# mainBoard.net
KiCad netlist of a schematic drawn in EAGLE
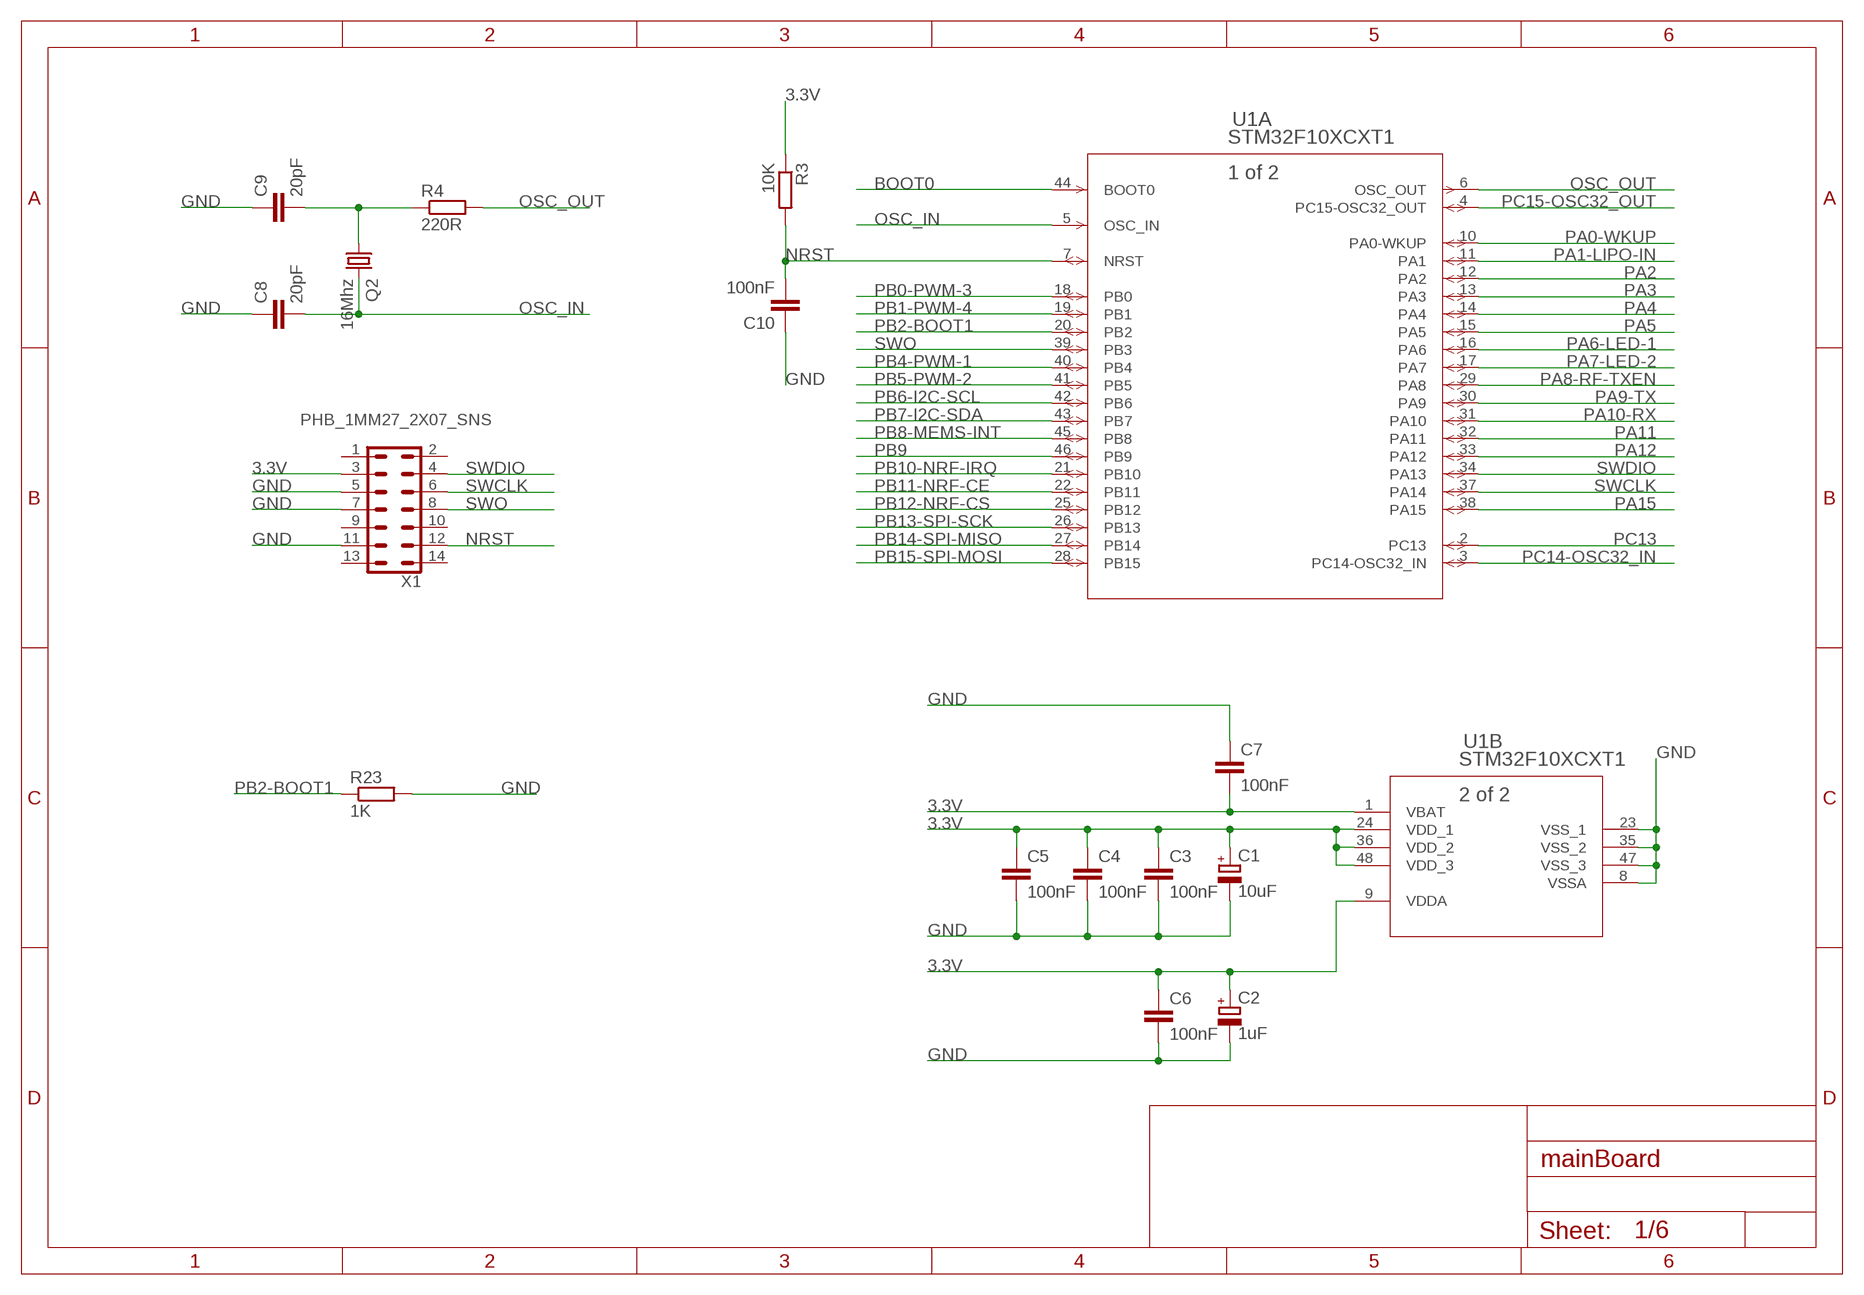
[diagram p0: schematic, sheet 1]
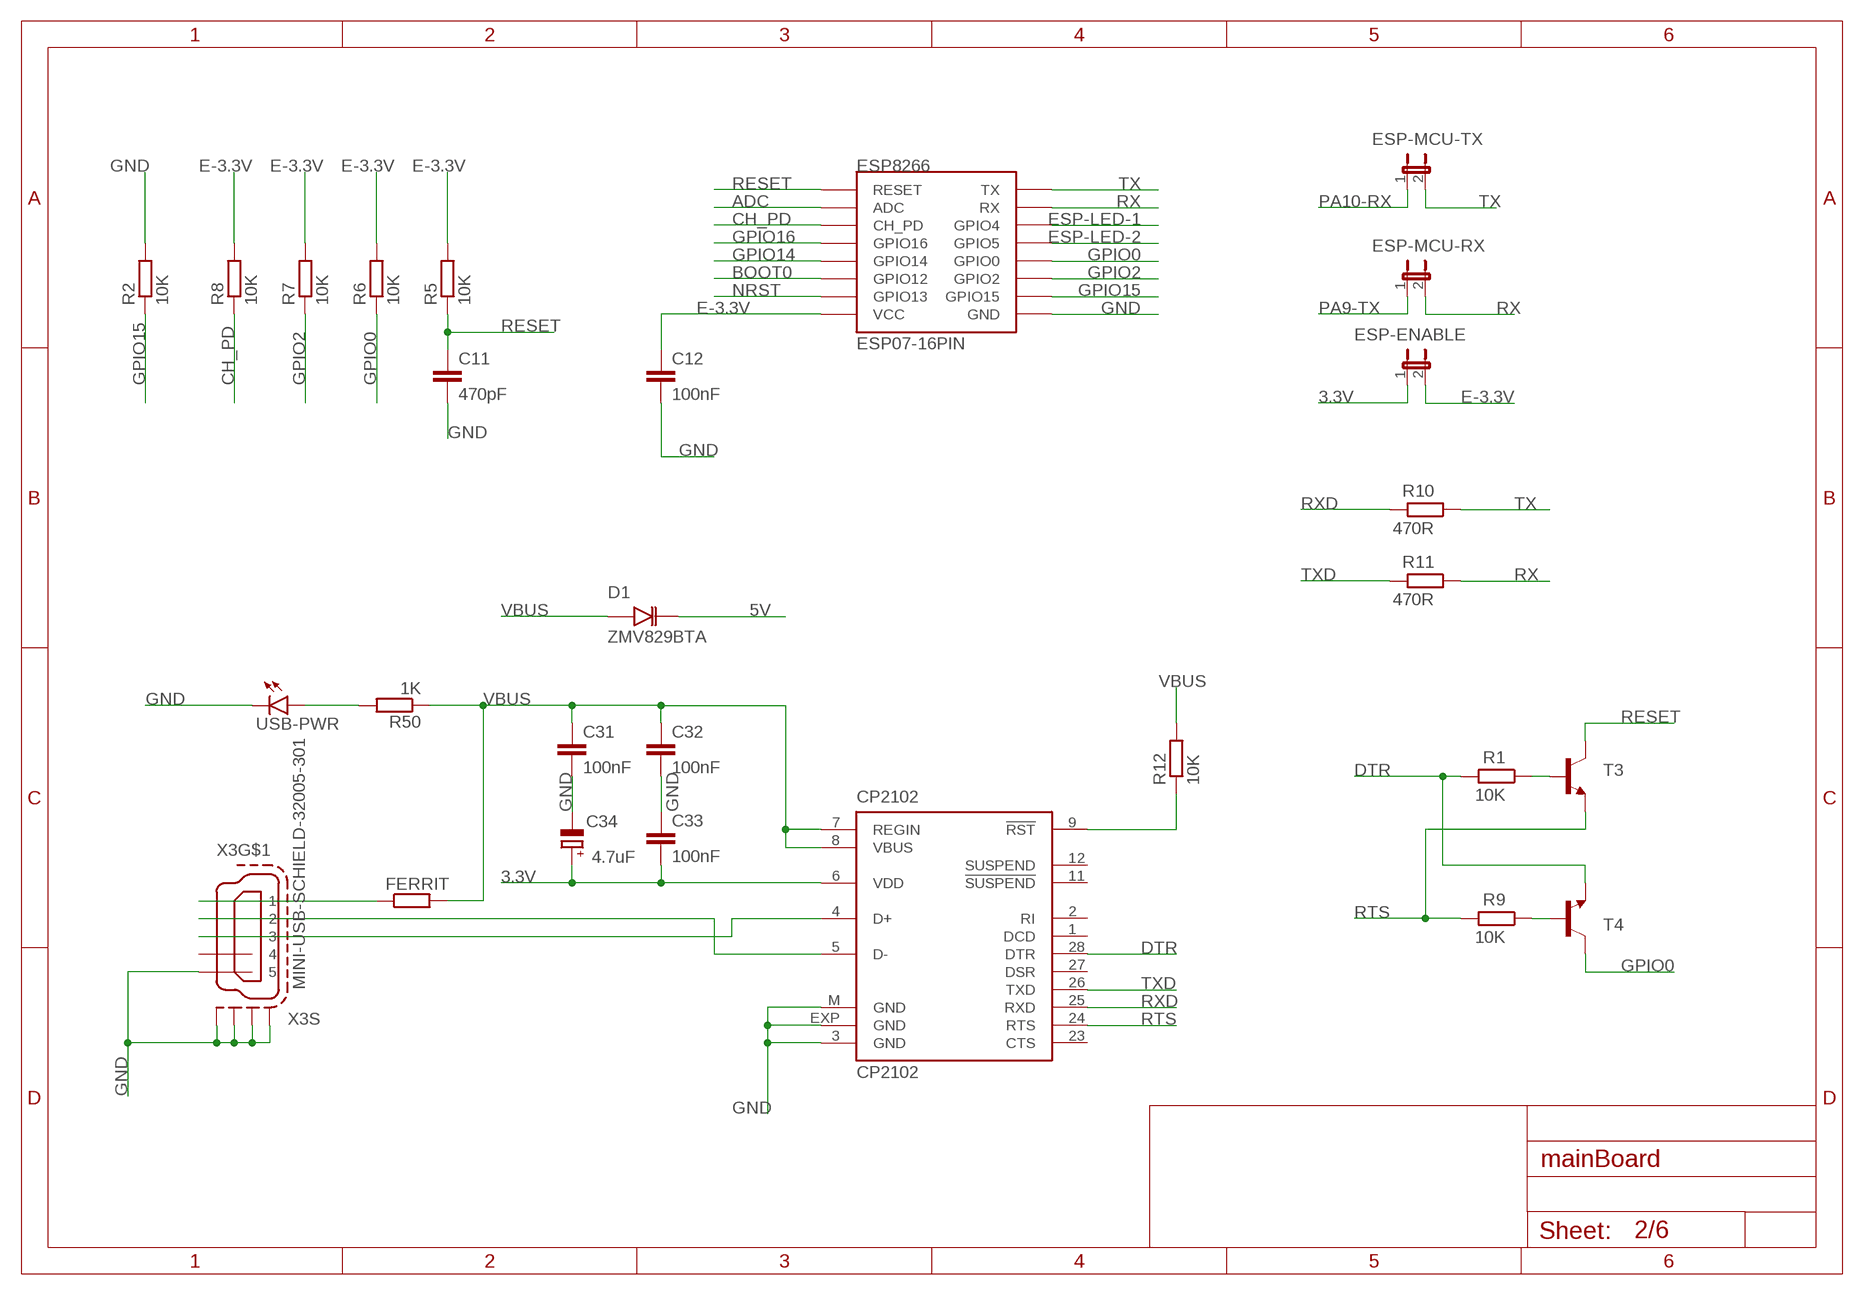
[diagram p1: schematic, sheet 2]
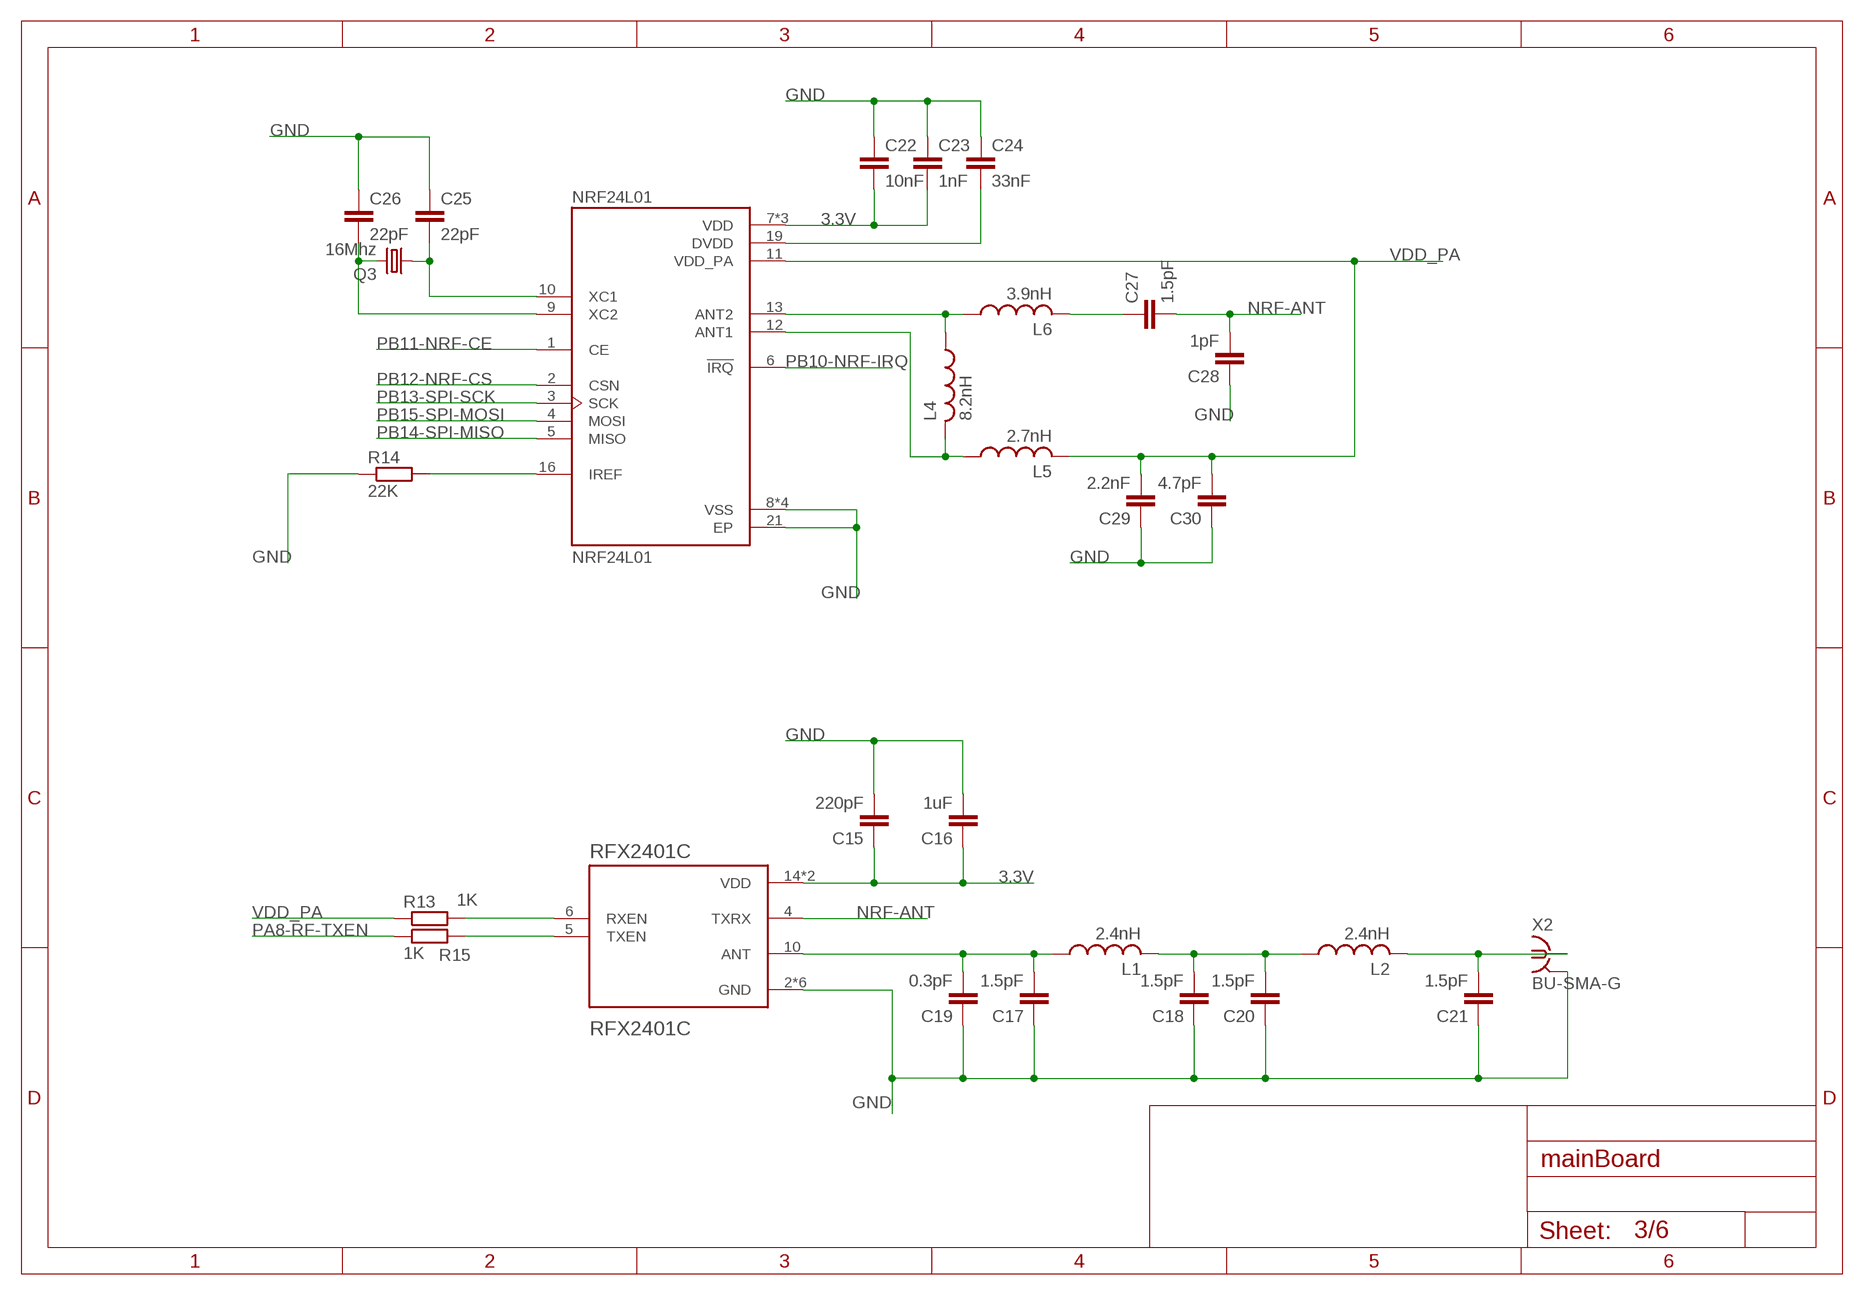
[diagram p2: schematic, sheet 3]
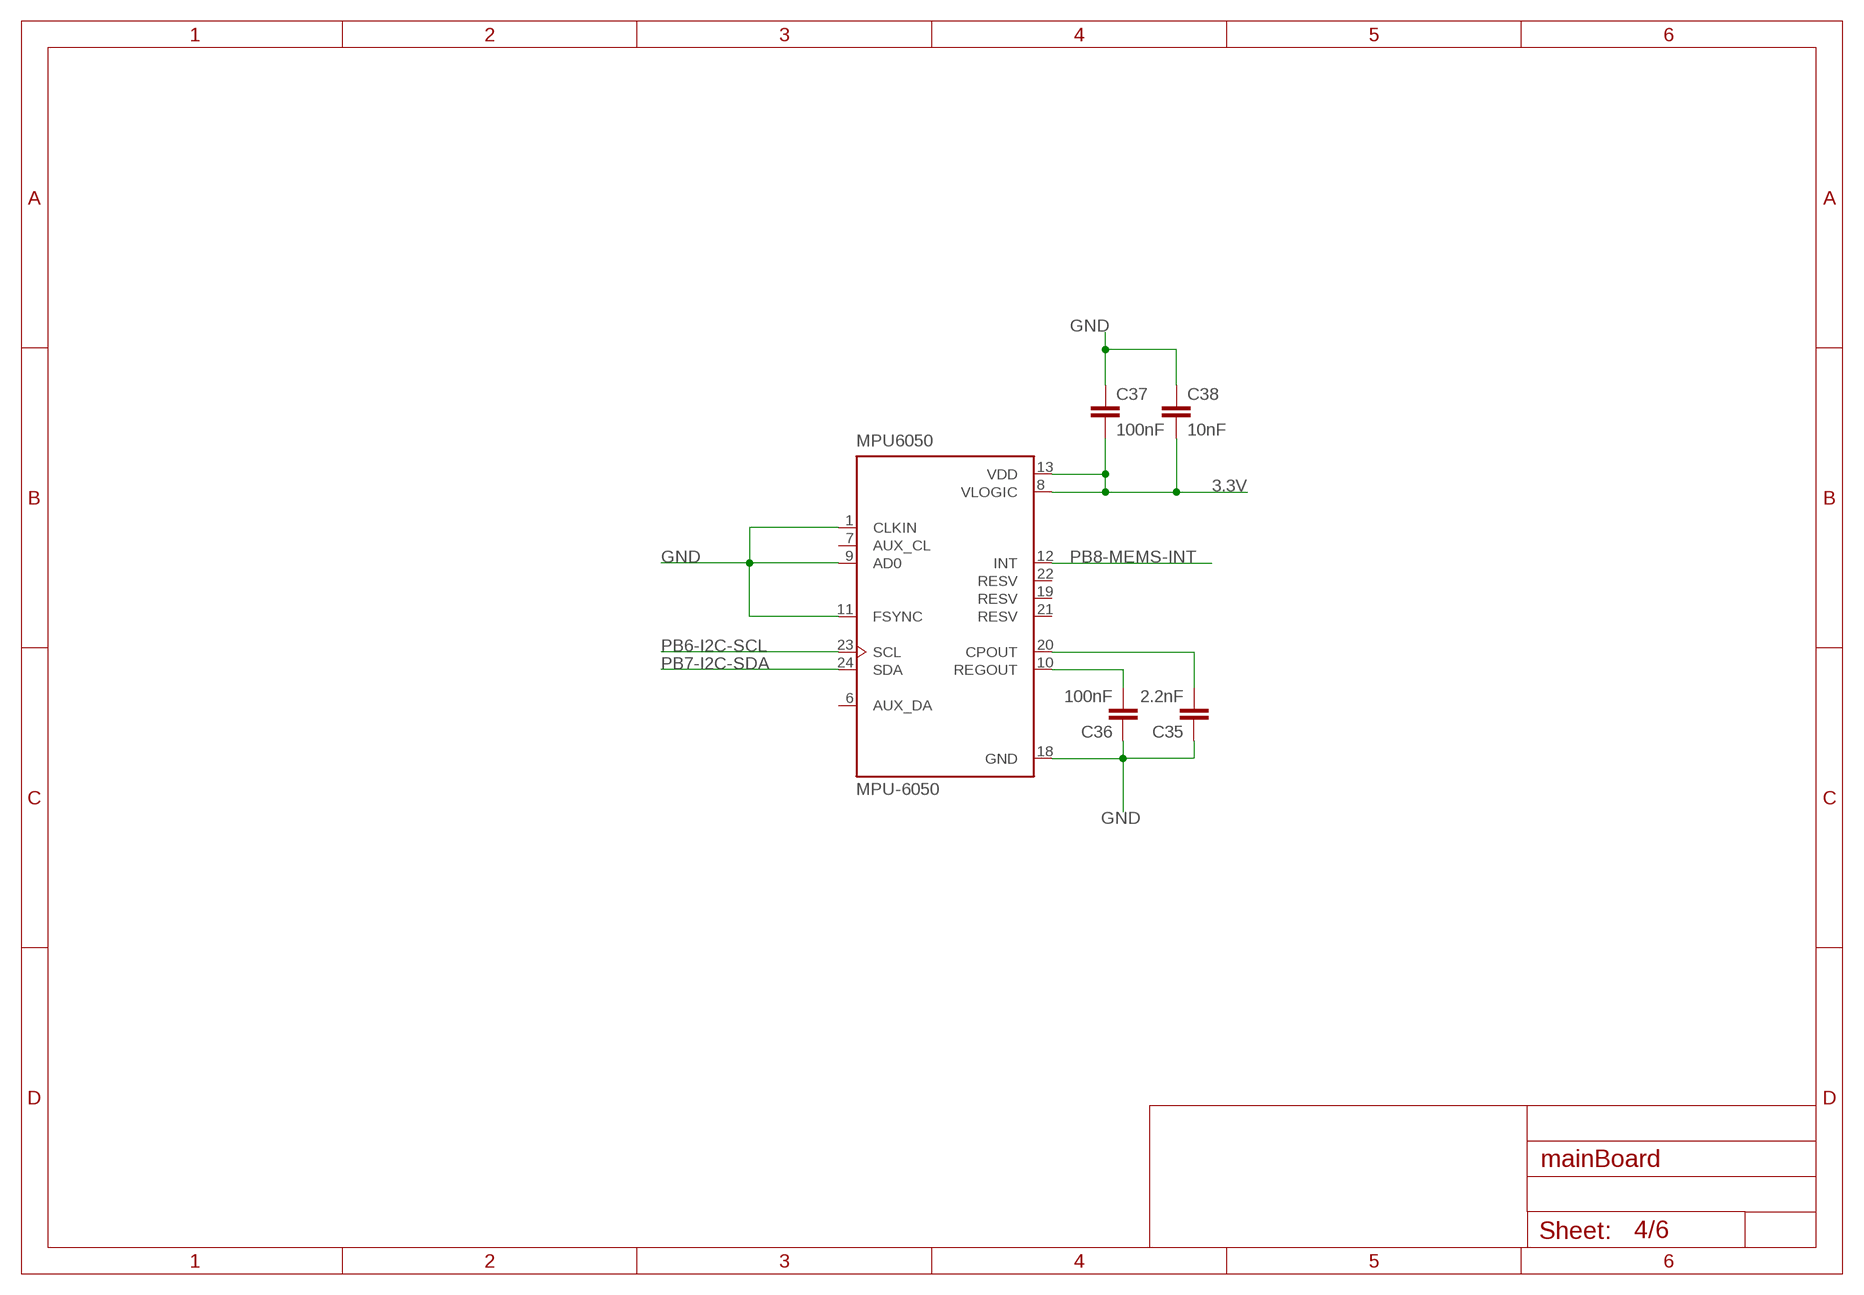
[diagram p3: schematic, sheet 4]
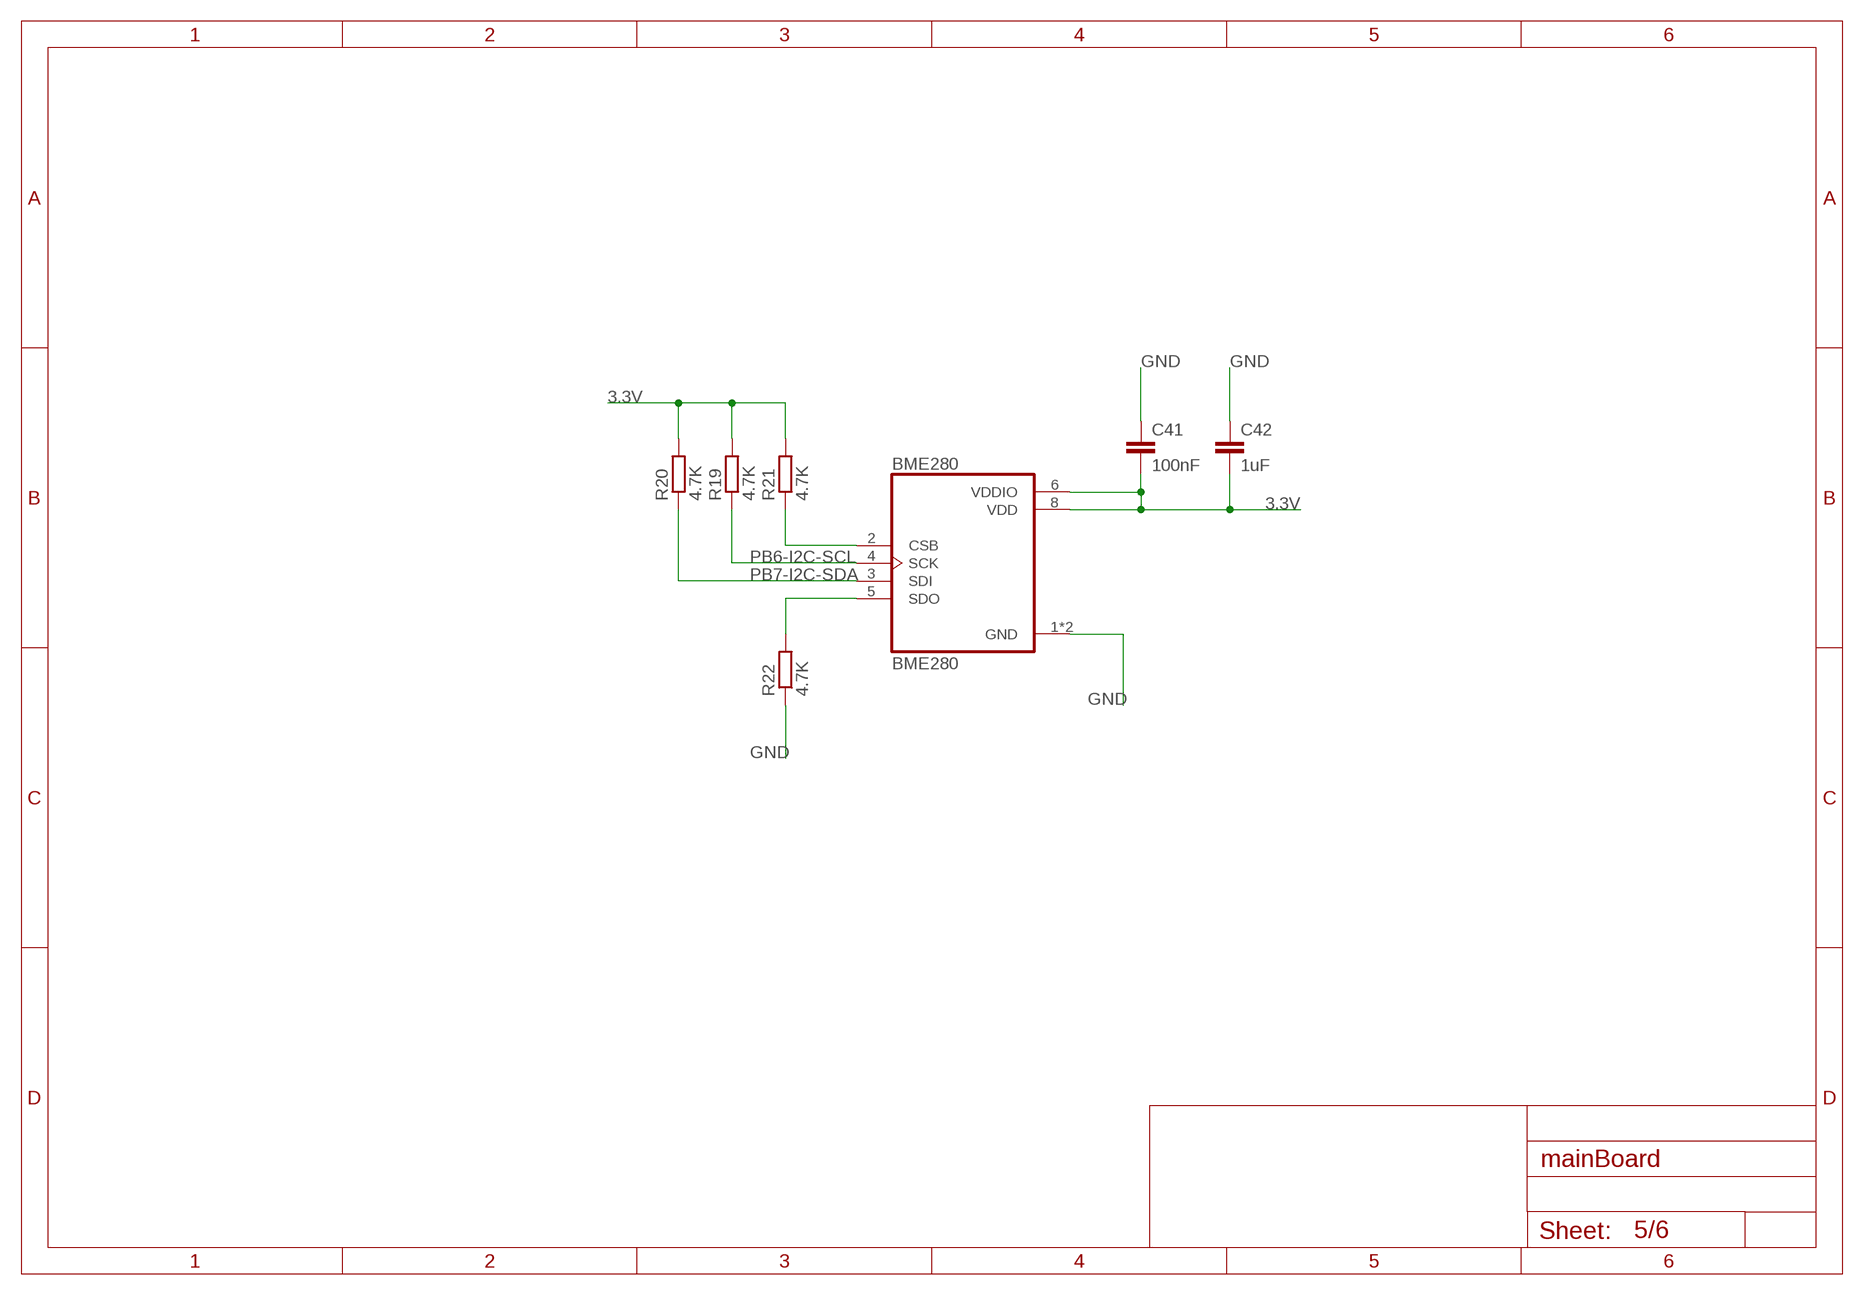
[diagram p4: schematic, sheet 5]
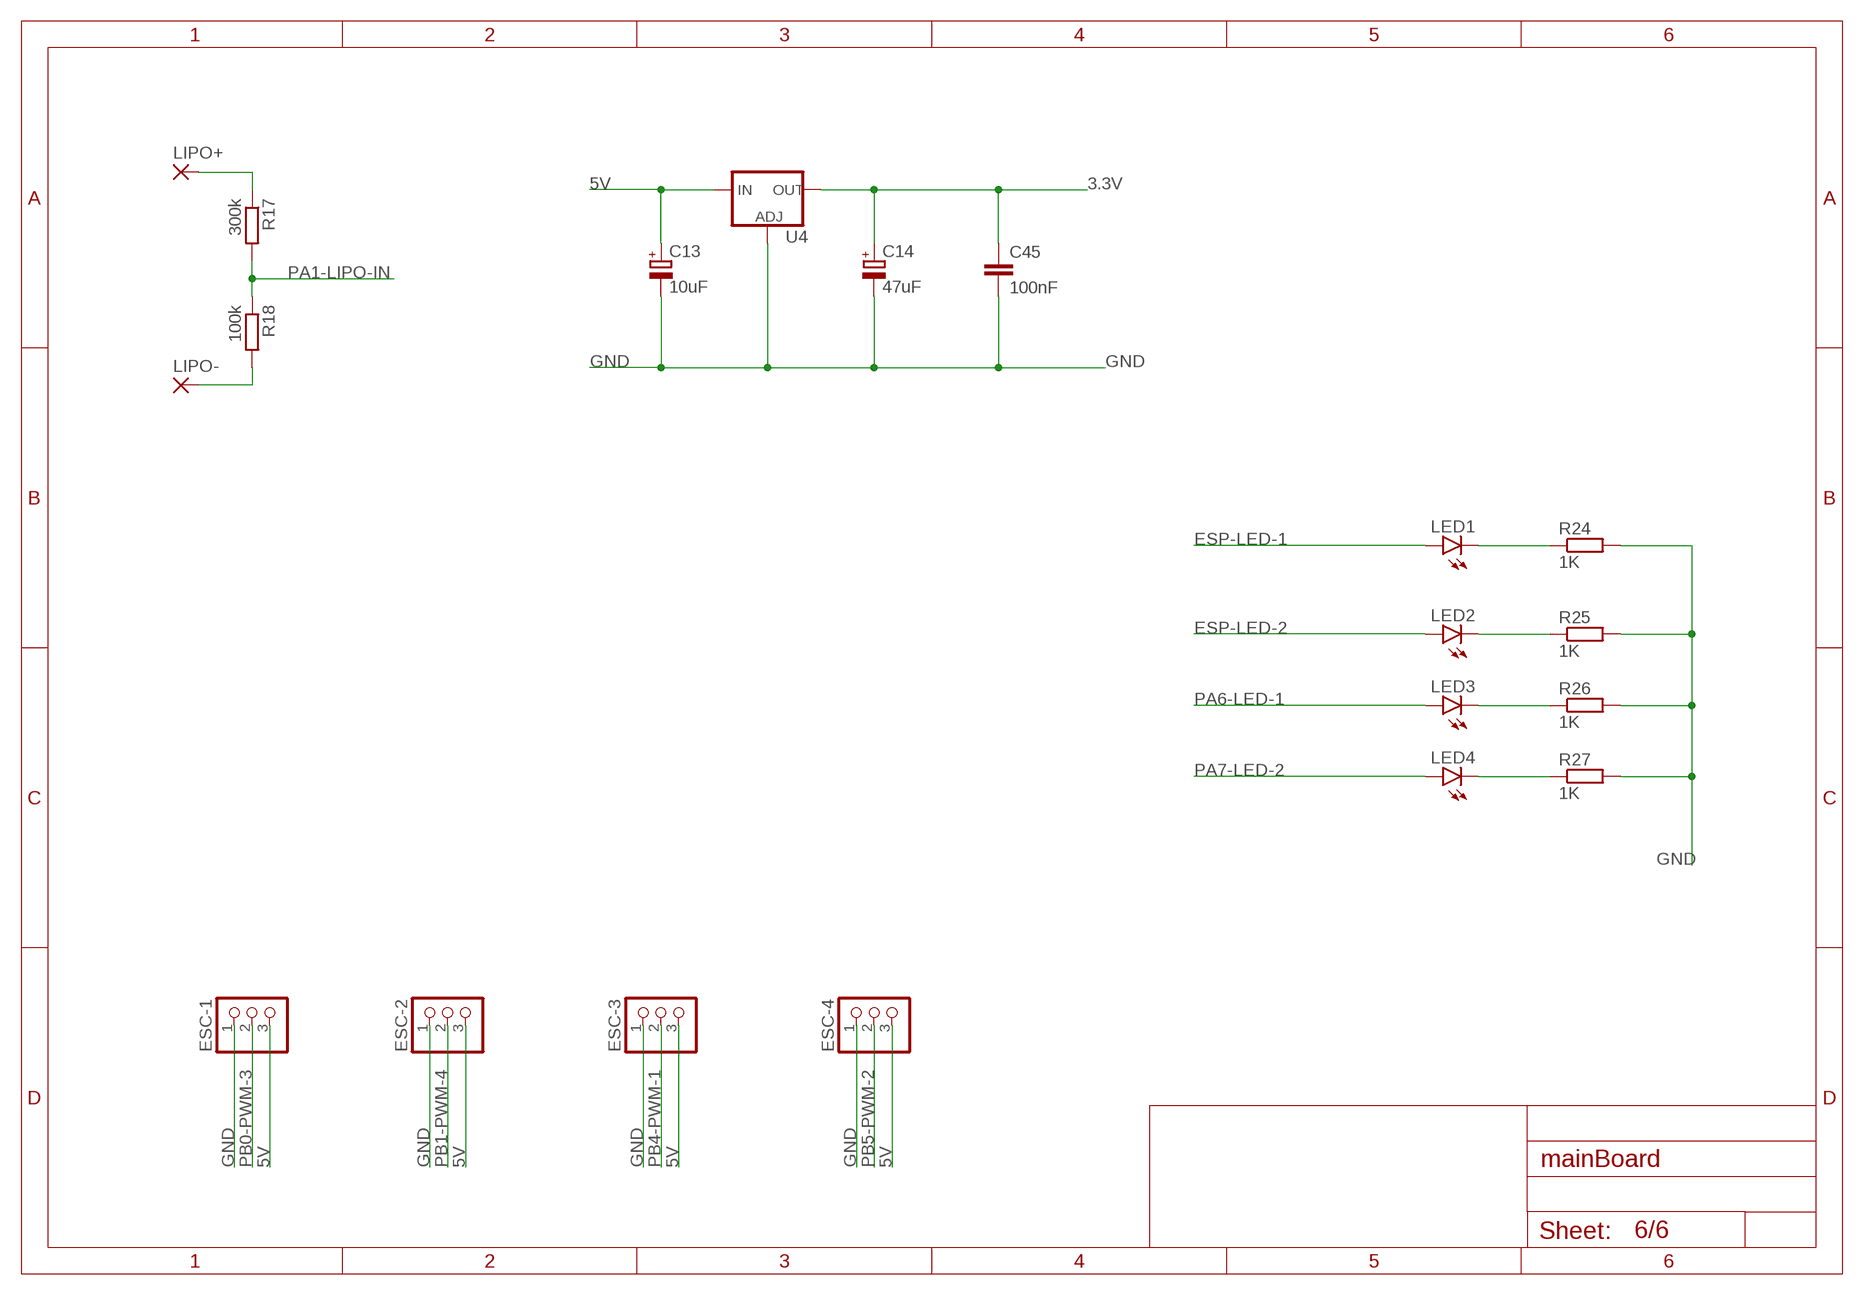
[diagram p5: schematic, sheet 6]

(export (version "E")
  (design (tool "Eeschema 10.0.6"))
  (components
    (comp (ref "C13")
      (value "10uF")
      (footprint "eagle-import:SMC_A")
      (libsource (lib "eagle-import") (part "CPOL-EUSMCA"))
    )
    (comp (ref "C14")
      (value "47uF")
      (footprint "eagle-import:SMC_A")
      (libsource (lib "eagle-import") (part "CPOL-EUSMCA"))
    )
    (comp (ref "C45")
      (value "100nF")
      (footprint "eagle-import:C0805")
      (libsource (lib "eagle-import") (part "C-EUC0805"))
    )
    (comp (ref "ESC-1")
      (value "PINHD-1X3")
      (footprint "eagle-import:1X03")
      (libsource (lib "eagle-import") (part "PINHD-1X3"))
    )
    (comp (ref "ESC-2")
      (value "PINHD-1X3")
      (footprint "eagle-import:1X03")
      (libsource (lib "eagle-import") (part "PINHD-1X3"))
    )
    (comp (ref "ESC-3")
      (value "PINHD-1X3")
      (footprint "eagle-import:1X03")
      (libsource (lib "eagle-import") (part "PINHD-1X3"))
    )
    (comp (ref "ESC-4")
      (value "PINHD-1X3")
      (footprint "eagle-import:1X03")
      (libsource (lib "eagle-import") (part "PINHD-1X3"))
    )
    (comp (ref "LED1")
      (value "LEDCHIPLED_0805")
      (footprint "eagle-import:CHIPLED_0805")
      (libsource (lib "eagle-import") (part "LEDCHIPLED_0805"))
    )
    (comp (ref "LED2")
      (value "LEDCHIPLED_0805")
      (footprint "eagle-import:CHIPLED_0805")
      (libsource (lib "eagle-import") (part "LEDCHIPLED_0805"))
    )
    (comp (ref "LED3")
      (value "LEDCHIPLED_0805")
      (footprint "eagle-import:CHIPLED_0805")
      (libsource (lib "eagle-import") (part "LEDCHIPLED_0805"))
    )
    (comp (ref "LED4")
      (value "LEDCHIPLED_0805")
      (footprint "eagle-import:CHIPLED_0805")
      (libsource (lib "eagle-import") (part "LEDCHIPLED_0805"))
    )
    (comp (ref "LIPO+")
      (value "2,15/1,0")
      (footprint "eagle-import:2,15_1,0")
      (libsource (lib "eagle-import") (part "2,15/1,0"))
    )
    (comp (ref "LIPO-")
      (value "2,15/1,0")
      (footprint "eagle-import:2,15_1,0")
      (libsource (lib "eagle-import") (part "2,15/1,0"))
    )
    (comp (ref "R17")
      (value "300k")
      (footprint "eagle-import:R0805")
      (libsource (lib "eagle-import") (part "R-EU_R0805"))
    )
    (comp (ref "R18")
      (value "100k")
      (footprint "eagle-import:R0805")
      (libsource (lib "eagle-import") (part "R-EU_R0805"))
    )
    (comp (ref "R24")
      (value "1K")
      (footprint "eagle-import:R0805")
      (libsource (lib "eagle-import") (part "R-EU_R0805"))
    )
    (comp (ref "R25")
      (value "1K")
      (footprint "eagle-import:R0805")
      (libsource (lib "eagle-import") (part "R-EU_R0805"))
    )
    (comp (ref "R26")
      (value "1K")
      (footprint "eagle-import:R0805")
      (libsource (lib "eagle-import") (part "R-EU_R0805"))
    )
    (comp (ref "R27")
      (value "1K")
      (footprint "eagle-import:R0805")
      (libsource (lib "eagle-import") (part "R-EU_R0805"))
    )
    (comp (ref "U4")
      (value "V_REG_LM1117SOT223")
      (footprint "eagle-import:SOT223")
      (libsource (lib "eagle-import") (part "V_REG_LM1117SOT223"))
    )
    (comp (ref "C11")
      (value "470pF")
      (footprint "eagle-import:C0805")
      (libsource (lib "eagle-import") (part "C-EUC0805"))
    )
    (comp (ref "C12")
      (value "100nF")
      (footprint "eagle-import:C0805")
      (libsource (lib "eagle-import") (part "C-EUC0805"))
    )
    (comp (ref "C31")
      (value "100nF")
      (footprint "eagle-import:C0805")
      (libsource (lib "eagle-import") (part "C-EUC0805"))
    )
    (comp (ref "C32")
      (value "100nF")
      (footprint "eagle-import:C0805")
      (libsource (lib "eagle-import") (part "C-EUC0805"))
    )
    (comp (ref "C33")
      (value "100nF")
      (footprint "eagle-import:C0805")
      (libsource (lib "eagle-import") (part "C-EUC0805"))
    )
    (comp (ref "C34")
      (value "4.7uF")
      (footprint "eagle-import:SMC_A")
      (libsource (lib "eagle-import") (part "CPOL-EUSMCA"))
    )
    (comp (ref "CP2102")
      (value "CP2102")
      (footprint "eagle-import:MLP28")
      (fields (field (name "MF") "FARNELL") (field (name "MPN") "CP2102-GM"))
      (libsource (lib "eagle-import") (part "CP2102"))
    )
    (comp (ref "D1")
      (value "ZMV829BTA")
      (footprint "eagle-import:SOD2512X116N")
      (fields (field (name "MF") "Diodes Inc."))
      (libsource (lib "eagle-import") (part "ZMV829BTA"))
    )
    (comp (ref "ESP-ENABLE")
      (value "JP1E")
      (footprint "eagle-import:JP1")
      (libsource (lib "eagle-import") (part "JP1E"))
    )
    (comp (ref "ESP-MCU-RX")
      (value "JP1E")
      (footprint "eagle-import:JP1")
      (libsource (lib "eagle-import") (part "JP1E"))
    )
    (comp (ref "ESP-MCU-TX")
      (value "JP1E")
      (footprint "eagle-import:JP1")
      (libsource (lib "eagle-import") (part "JP1E"))
    )
    (comp (ref "ESP8266")
      (value "ESP07-16PIN")
      (footprint "eagle-import:ESP07-16PIN")
      (libsource (lib "eagle-import") (part "ESP07-16PIN"))
    )
    (comp (ref "FERRIT")
      (value "R-EU_R0805")
      (footprint "eagle-import:R0805")
      (libsource (lib "eagle-import") (part "R-EU_R0805"))
    )
    (comp (ref "R1")
      (value "10K")
      (footprint "eagle-import:R0805")
      (libsource (lib "eagle-import") (part "R-EU_R0805"))
    )
    (comp (ref "R2")
      (value "10K")
      (footprint "eagle-import:R0805")
      (libsource (lib "eagle-import") (part "R-EU_R0805"))
    )
    (comp (ref "R5")
      (value "10K")
      (footprint "eagle-import:R0805")
      (libsource (lib "eagle-import") (part "R-EU_R0805"))
    )
    (comp (ref "R6")
      (value "10K")
      (footprint "eagle-import:R0805")
      (libsource (lib "eagle-import") (part "R-EU_R0805"))
    )
    (comp (ref "R7")
      (value "10K")
      (footprint "eagle-import:R0805")
      (libsource (lib "eagle-import") (part "R-EU_R0805"))
    )
    (comp (ref "R8")
      (value "10K")
      (footprint "eagle-import:R0805")
      (libsource (lib "eagle-import") (part "R-EU_R0805"))
    )
    (comp (ref "R9")
      (value "10K")
      (footprint "eagle-import:R0805")
      (libsource (lib "eagle-import") (part "R-EU_R0805"))
    )
    (comp (ref "R10")
      (value "470R")
      (footprint "eagle-import:R0805")
      (libsource (lib "eagle-import") (part "R-EU_R0805"))
    )
    (comp (ref "R11")
      (value "470R")
      (footprint "eagle-import:R0805")
      (libsource (lib "eagle-import") (part "R-EU_R0805"))
    )
    (comp (ref "R12")
      (value "10K")
      (footprint "eagle-import:R0805")
      (libsource (lib "eagle-import") (part "R-EU_R0805"))
    )
    (comp (ref "R50")
      (value "1K")
      (footprint "eagle-import:R0805")
      (libsource (lib "eagle-import") (part "R-EU_R0805"))
    )
    (comp (ref "T3")
      (value "-NPN-SOT23-EBC")
      (footprint "eagle-import:SOT23-EBC")
      (libsource (lib "eagle-import") (part "-NPN-SOT23-EBC"))
    )
    (comp (ref "T4")
      (value "-NPN-SOT23-EBC")
      (footprint "eagle-import:SOT23-EBC")
      (libsource (lib "eagle-import") (part "-NPN-SOT23-EBC"))
    )
    (comp (ref "USB-PWR")
      (value "LEDCHIPLED_0805")
      (footprint "eagle-import:CHIPLED_0805")
      (libsource (lib "eagle-import") (part "LEDCHIPLED_0805"))
    )
    (comp (ref "X3")
      (value "MINI-USB-SCHIELD-32005-301")
      (footprint "eagle-import:32005-301")
      (libsource (lib "eagle-import") (part "MINI-USB-SCHIELD-32005-301"))
    )
    (comp (ref "BME280")
      (value "BME280")
      (footprint "eagle-import:PSON65P250X250X100-8N")
      (fields (field (name "MF") "Bosch"))
      (libsource (lib "eagle-import") (part "BME280"))
    )
    (comp (ref "C41")
      (value "100nF")
      (footprint "eagle-import:C0805")
      (libsource (lib "eagle-import") (part "C-EUC0805"))
    )
    (comp (ref "C42")
      (value "1uF")
      (footprint "eagle-import:C0805")
      (libsource (lib "eagle-import") (part "C-EUC0805"))
    )
    (comp (ref "R19")
      (value "4.7K")
      (footprint "eagle-import:R0805")
      (libsource (lib "eagle-import") (part "R-EU_R0805"))
    )
    (comp (ref "R20")
      (value "4.7K")
      (footprint "eagle-import:R0805")
      (libsource (lib "eagle-import") (part "R-EU_R0805"))
    )
    (comp (ref "R21")
      (value "4.7K")
      (footprint "eagle-import:R0805")
      (libsource (lib "eagle-import") (part "R-EU_R0805"))
    )
    (comp (ref "R22")
      (value "4.7K")
      (footprint "eagle-import:R0805")
      (libsource (lib "eagle-import") (part "R-EU_R0805"))
    )
    (comp (ref "C1")
      (value "10uF")
      (footprint "eagle-import:SMC_A")
      (libsource (lib "eagle-import") (part "CPOL-EUSMCA"))
    )
    (comp (ref "C2")
      (value "1uF")
      (footprint "eagle-import:SMC_A")
      (libsource (lib "eagle-import") (part "CPOL-EUSMCA"))
    )
    (comp (ref "C3")
      (value "100nF")
      (footprint "eagle-import:C0805")
      (libsource (lib "eagle-import") (part "C-EUC0805"))
    )
    (comp (ref "C4")
      (value "100nF")
      (footprint "eagle-import:C0805")
      (libsource (lib "eagle-import") (part "C-EUC0805"))
    )
    (comp (ref "C5")
      (value "100nF")
      (footprint "eagle-import:C0805")
      (libsource (lib "eagle-import") (part "C-EUC0805"))
    )
    (comp (ref "C6")
      (value "100nF")
      (footprint "eagle-import:C0805")
      (libsource (lib "eagle-import") (part "C-EUC0805"))
    )
    (comp (ref "C7")
      (value "100nF")
      (footprint "eagle-import:C0805")
      (libsource (lib "eagle-import") (part "C-EUC0805"))
    )
    (comp (ref "C8")
      (value "20pF")
      (footprint "eagle-import:C0805")
      (libsource (lib "eagle-import") (part "C-EUC0805"))
    )
    (comp (ref "C9")
      (value "20pF")
      (footprint "eagle-import:C0805")
      (libsource (lib "eagle-import") (part "C-EUC0805"))
    )
    (comp (ref "C10")
      (value "100nF")
      (footprint "eagle-import:C0805")
      (libsource (lib "eagle-import") (part "C-EUC0805"))
    )
    (comp (ref "Q2")
      (value "16Mhz")
      (footprint "eagle-import:HC49_S")
      (libsource (lib "eagle-import") (part "CRYSTALHC49S"))
    )
    (comp (ref "R3")
      (value "10K")
      (footprint "eagle-import:R0805")
      (libsource (lib "eagle-import") (part "R-EU_R0805"))
    )
    (comp (ref "R4")
      (value "220R")
      (footprint "eagle-import:R0805")
      (libsource (lib "eagle-import") (part "R-EU_R0805"))
    )
    (comp (ref "R23")
      (value "1K")
      (footprint "eagle-import:R0805")
      (libsource (lib "eagle-import") (part "R-EU_R0805"))
    )
    (comp (ref "U1")
      (value "STM32F10XCXT1")
      (footprint "eagle-import:LQFP48-7X7MM")
      (fields (field (name "COPYRIGHT") "Copyright (C) 2016 Accelerated Designs. All rights reserved"))
      (libsource (lib "eagle-import") (part "STM32F10XCXT1"))
    )
    (comp (ref "X1")
      (value "PHB_1MM27_2X07_SNS")
      (footprint "eagle-import:PHB_1MM27_2X07_SNS")
      (libsource (lib "eagle-import") (part "PHB_1MM27_2X07_SNS"))
    )
    (comp (ref "C35")
      (value "2.2nF")
      (footprint "eagle-import:C0805")
      (libsource (lib "eagle-import") (part "C-EUC0805"))
    )
    (comp (ref "C36")
      (value "100nF")
      (footprint "eagle-import:C0805")
      (libsource (lib "eagle-import") (part "C-EUC0805"))
    )
    (comp (ref "C37")
      (value "100nF")
      (footprint "eagle-import:C0805")
      (libsource (lib "eagle-import") (part "C-EUC0805"))
    )
    (comp (ref "C38")
      (value "10nF")
      (footprint "eagle-import:C0805")
      (libsource (lib "eagle-import") (part "C-EUC0805"))
    )
    (comp (ref "MPU6050")
      (value "MPU-6050")
      (footprint "eagle-import:QFN50P400X400X95-24N")
      (fields (field (name "MF") "TDK InvenSense"))
      (libsource (lib "eagle-import") (part "MPU-6050"))
    )
    (comp (ref "C15")
      (value "220pF")
      (footprint "eagle-import:C0805")
      (libsource (lib "eagle-import") (part "C-EUC0805"))
    )
    (comp (ref "C16")
      (value "1uF")
      (footprint "eagle-import:C0805")
      (libsource (lib "eagle-import") (part "C-EUC0805"))
    )
    (comp (ref "C17")
      (value "1.5pF")
      (footprint "eagle-import:C0805")
      (libsource (lib "eagle-import") (part "C-EUC0805"))
    )
    (comp (ref "C18")
      (value "1.5pF")
      (footprint "eagle-import:C0805")
      (libsource (lib "eagle-import") (part "C-EUC0805"))
    )
    (comp (ref "C19")
      (value "0.3pF")
      (footprint "eagle-import:C0805")
      (libsource (lib "eagle-import") (part "C-EUC0805"))
    )
    (comp (ref "C20")
      (value "1.5pF")
      (footprint "eagle-import:C0805")
      (libsource (lib "eagle-import") (part "C-EUC0805"))
    )
    (comp (ref "C21")
      (value "1.5pF")
      (footprint "eagle-import:C0805")
      (libsource (lib "eagle-import") (part "C-EUC0805"))
    )
    (comp (ref "C22")
      (value "10nF")
      (footprint "eagle-import:C0805")
      (libsource (lib "eagle-import") (part "C-EUC0805"))
    )
    (comp (ref "C23")
      (value "1nF")
      (footprint "eagle-import:C0805")
      (libsource (lib "eagle-import") (part "C-EUC0805"))
    )
    (comp (ref "C24")
      (value "33nF")
      (footprint "eagle-import:C0805")
      (libsource (lib "eagle-import") (part "C-EUC0805"))
    )
    (comp (ref "C25")
      (value "22pF")
      (footprint "eagle-import:C0805")
      (libsource (lib "eagle-import") (part "C-EUC0805"))
    )
    (comp (ref "C26")
      (value "22pF")
      (footprint "eagle-import:C0805")
      (libsource (lib "eagle-import") (part "C-EUC0805"))
    )
    (comp (ref "C27")
      (value "1.5pF")
      (footprint "eagle-import:C0805")
      (libsource (lib "eagle-import") (part "C-EUC0805"))
    )
    (comp (ref "C28")
      (value "1pF")
      (footprint "eagle-import:C0805")
      (libsource (lib "eagle-import") (part "C-EUC0805"))
    )
    (comp (ref "C29")
      (value "2.2nF")
      (footprint "eagle-import:C0805")
      (libsource (lib "eagle-import") (part "C-EUC0805"))
    )
    (comp (ref "C30")
      (value "4.7pF")
      (footprint "eagle-import:C0805")
      (libsource (lib "eagle-import") (part "C-EUC0805"))
    )
    (comp (ref "L1")
      (value "2.4nH")
      (footprint "eagle-import:L2012C")
      (libsource (lib "eagle-import") (part "L-USL2012C"))
    )
    (comp (ref "L2")
      (value "2.4nH")
      (footprint "eagle-import:L2012C")
      (libsource (lib "eagle-import") (part "L-USL2012C"))
    )
    (comp (ref "L4")
      (value "8.2nH")
      (footprint "eagle-import:L2012C")
      (libsource (lib "eagle-import") (part "L-USL2012C"))
    )
    (comp (ref "L5")
      (value "2.7nH")
      (footprint "eagle-import:L2012C")
      (libsource (lib "eagle-import") (part "L-USL2012C"))
    )
    (comp (ref "L6")
      (value "3.9nH")
      (footprint "eagle-import:L2012C")
      (libsource (lib "eagle-import") (part "L-USL2012C"))
    )
    (comp (ref "NRF24L01")
      (value "NRF24L01")
      (footprint "eagle-import:QFN50P400X400X95-21N")
      (fields (field (name "MF") "Nordic"))
      (libsource (lib "eagle-import") (part "NRF24L01"))
    )
    (comp (ref "Q3")
      (value "16Mhz")
      (footprint "eagle-import:HC49_S")
      (libsource (lib "eagle-import") (part "CRYSTALHC49S"))
    )
    (comp (ref "R13")
      (value "1K")
      (footprint "eagle-import:R0805")
      (libsource (lib "eagle-import") (part "R-EU_R0805"))
    )
    (comp (ref "R14")
      (value "22K")
      (footprint "eagle-import:R0805")
      (libsource (lib "eagle-import") (part "R-EU_R0805"))
    )
    (comp (ref "R15")
      (value "1K")
      (footprint "eagle-import:R0805")
      (libsource (lib "eagle-import") (part "R-EU_R0805"))
    )
    (comp (ref "RFX2401C")
      (value "RFX2401C")
      (footprint "eagle-import:QFN50P300X300X60-17N")
      (fields (field (name "MF") "Skyworks Solutions"))
      (libsource (lib "eagle-import") (part "RFX2401C"))
    )
    (comp (ref "X2")
      (value "BU-SMA-G")
      (footprint "eagle-import:BU-SMA-G")
      (libsource (lib "eagle-import") (part "BU-SMA-G"))
    )
  )
  (nets
    (net (code "1") (name "3.3V") (class "Default")
      (node (ref "BME280") (pin "6") (pinfunction "VDDIO_6") (pintype "power_in"))
      (node (ref "BME280") (pin "8") (pinfunction "VDD_8") (pintype "power_in"))
      (node (ref "C1") (pin "+") (pinfunction "+_+") (pintype "passive"))
      (node (ref "C14") (pin "+") (pinfunction "+_+") (pintype "passive"))
      (node (ref "C15") (pin "1") (pinfunction "1_1") (pintype "passive"))
      (node (ref "C16") (pin "1") (pinfunction "1_1") (pintype "passive"))
      (node (ref "C2") (pin "+") (pinfunction "+_+") (pintype "passive"))
      (node (ref "C22") (pin "2") (pinfunction "2_2") (pintype "passive"))
      (node (ref "C23") (pin "2") (pinfunction "2_2") (pintype "passive"))
      (node (ref "C3") (pin "1") (pinfunction "1_1") (pintype "passive"))
      (node (ref "C33") (pin "2") (pinfunction "2_2") (pintype "passive"))
      (node (ref "C34") (pin "+") (pinfunction "+_+") (pintype "passive"))
      (node (ref "C37") (pin "2") (pinfunction "2_2") (pintype "passive"))
      (node (ref "C38") (pin "2") (pinfunction "2_2") (pintype "passive"))
      (node (ref "C4") (pin "1") (pinfunction "1_1") (pintype "passive"))
      (node (ref "C41") (pin "2") (pinfunction "2_2") (pintype "passive"))
      (node (ref "C42") (pin "2") (pinfunction "2_2") (pintype "passive"))
      (node (ref "C45") (pin "1") (pinfunction "1_1") (pintype "passive"))
      (node (ref "C5") (pin "1") (pinfunction "1_1") (pintype "passive"))
      (node (ref "C6") (pin "1") (pinfunction "1_1") (pintype "passive"))
      (node (ref "C7") (pin "2") (pinfunction "2_2") (pintype "passive"))
      (node (ref "CP2102") (pin "6") (pinfunction "VDD_6") (pintype "power_in"))
      (node (ref "ESP-ENABLE") (pin "1") (pinfunction "1_1") (pintype "passive"))
      (node (ref "MPU6050") (pin "13") (pinfunction "VDD_13") (pintype "power_in"))
      (node (ref "MPU6050") (pin "8") (pinfunction "VLOGIC_8") (pintype "power_in"))
      (node (ref "NRF24L01") (pin "15") (pinfunction "VDD_15") (pintype "power_in"))
      (node (ref "NRF24L01") (pin "18") (pinfunction "VDD_18") (pintype "power_in"))
      (node (ref "NRF24L01") (pin "7") (pinfunction "VDD_7") (pintype "power_in"))
      (node (ref "R19") (pin "2") (pinfunction "2_2") (pintype "passive"))
      (node (ref "R20") (pin "2") (pinfunction "2_2") (pintype "passive"))
      (node (ref "R21") (pin "2") (pinfunction "2_2") (pintype "passive"))
      (node (ref "R3") (pin "1") (pinfunction "1_1") (pintype "passive"))
      (node (ref "RFX2401C") (pin "14") (pinfunction "VDD_14") (pintype "power_in"))
      (node (ref "RFX2401C") (pin "16") (pinfunction "VDD_16") (pintype "power_in"))
      (node (ref "U1") (pin "1") (pinfunction "VBAT_1") (pintype "power_in"))
      (node (ref "U1") (pin "24") (pinfunction "VDD_1_24") (pintype "power_in"))
      (node (ref "U1") (pin "36") (pinfunction "VDD_2_36") (pintype "power_in"))
      (node (ref "U1") (pin "48") (pinfunction "VDD_3_48") (pintype "power_in"))
      (node (ref "U1") (pin "9") (pinfunction "VDDA_9") (pintype "power_in"))
      (node (ref "U4") (pin "2") (pinfunction "OUT_2") (pintype "output"))
      (node (ref "U4") (pin "4") (pinfunction "OUT_4") (pintype "output"))
      (node (ref "X1") (pin "3") (pinfunction "3_3") (pintype "passive"))
    )
    (net (code "2") (name "5V") (class "Default")
      (node (ref "C13") (pin "+") (pinfunction "+_+") (pintype "passive"))
      (node (ref "D1") (pin "K") (pinfunction "K_K") (pintype "passive"))
      (node (ref "ESC-1") (pin "3") (pinfunction "3_3") (pintype "passive"))
      (node (ref "ESC-2") (pin "3") (pinfunction "3_3") (pintype "passive"))
      (node (ref "ESC-3") (pin "3") (pinfunction "3_3") (pintype "passive"))
      (node (ref "ESC-4") (pin "3") (pinfunction "3_3") (pintype "passive"))
      (node (ref "U4") (pin "3") (pinfunction "IN_3") (pintype "input"))
    )
    (net (code "3") (name "ADC") (class "Default")
      (node (ref "ESP8266") (pin "ADC") (pinfunction "ADC_ADC") (pintype "bidirectional"))
    )
    (net (code "4") (name "BOOT0") (class "Default")
      (node (ref "ESP8266") (pin "GPIO12") (pinfunction "GPIO12_GPIO12") (pintype "bidirectional"))
      (node (ref "U1") (pin "44") (pinfunction "BOOT0_44") (pintype "input"))
    )
    (net (code "5") (name "CH_PD") (class "Default")
      (node (ref "ESP8266") (pin "CH_PD") (pinfunction "CH_PD_CH_PD") (pintype "bidirectional"))
      (node (ref "R8") (pin "1") (pinfunction "1_1") (pintype "passive"))
    )
    (net (code "6") (name "DTR") (class "Default")
      (node (ref "CP2102") (pin "28") (pinfunction "DTR_28") (pintype "output"))
      (node (ref "R1") (pin "2") (pinfunction "2_2") (pintype "passive"))
      (node (ref "T4") (pin "E") (pinfunction "E_E") (pintype "passive"))
    )
    (net (code "7") (name "E-3.3V") (class "Default")
      (node (ref "C12") (pin "1") (pinfunction "1_1") (pintype "passive"))
      (node (ref "ESP-ENABLE") (pin "2") (pinfunction "2_2") (pintype "passive"))
      (node (ref "ESP8266") (pin "VCC") (pinfunction "VCC_VCC") (pintype "bidirectional"))
      (node (ref "R5") (pin "2") (pinfunction "2_2") (pintype "passive"))
      (node (ref "R6") (pin "2") (pinfunction "2_2") (pintype "passive"))
      (node (ref "R7") (pin "2") (pinfunction "2_2") (pintype "passive"))
      (node (ref "R8") (pin "2") (pinfunction "2_2") (pintype "passive"))
    )
    (net (code "8") (name "ESP-LED-1") (class "Default")
      (node (ref "ESP8266") (pin "GPIO4") (pinfunction "GPIO4_GPIO4") (pintype "bidirectional"))
      (node (ref "LED1") (pin "A") (pinfunction "A_A") (pintype "passive"))
    )
    (net (code "9") (name "ESP-LED-2") (class "Default")
      (node (ref "ESP8266") (pin "GPIO5") (pinfunction "GPIO5_GPIO5") (pintype "bidirectional"))
      (node (ref "LED2") (pin "A") (pinfunction "A_A") (pintype "passive"))
    )
    (net (code "10") (name "GND") (class "Default")
      (node (ref "BME280") (pin "1") (pinfunction "GND_1") (pintype "power_in"))
      (node (ref "BME280") (pin "7") (pinfunction "GND_7") (pintype "power_in"))
      (node (ref "C1") (pin "-") (pinfunction "-_-") (pintype "passive"))
      (node (ref "C10") (pin "1") (pinfunction "1_1") (pintype "passive"))
      (node (ref "C11") (pin "2") (pinfunction "2_2") (pintype "passive"))
      (node (ref "C12") (pin "2") (pinfunction "2_2") (pintype "passive"))
      (node (ref "C13") (pin "-") (pinfunction "-_-") (pintype "passive"))
      (node (ref "C14") (pin "-") (pinfunction "-_-") (pintype "passive"))
      (node (ref "C15") (pin "2") (pinfunction "2_2") (pintype "passive"))
      (node (ref "C16") (pin "2") (pinfunction "2_2") (pintype "passive"))
      (node (ref "C17") (pin "1") (pinfunction "1_1") (pintype "passive"))
      (node (ref "C18") (pin "1") (pinfunction "1_1") (pintype "passive"))
      (node (ref "C19") (pin "1") (pinfunction "1_1") (pintype "passive"))
      (node (ref "C2") (pin "-") (pinfunction "-_-") (pintype "passive"))
      (node (ref "C20") (pin "1") (pinfunction "1_1") (pintype "passive"))
      (node (ref "C21") (pin "1") (pinfunction "1_1") (pintype "passive"))
      (node (ref "C22") (pin "1") (pinfunction "1_1") (pintype "passive"))
      (node (ref "C23") (pin "1") (pinfunction "1_1") (pintype "passive"))
      (node (ref "C24") (pin "1") (pinfunction "1_1") (pintype "passive"))
      (node (ref "C25") (pin "1") (pinfunction "1_1") (pintype "passive"))
      (node (ref "C26") (pin "1") (pinfunction "1_1") (pintype "passive"))
      (node (ref "C28") (pin "1") (pinfunction "1_1") (pintype "passive"))
      (node (ref "C29") (pin "1") (pinfunction "1_1") (pintype "passive"))
      (node (ref "C3") (pin "2") (pinfunction "2_2") (pintype "passive"))
      (node (ref "C30") (pin "1") (pinfunction "1_1") (pintype "passive"))
      (node (ref "C31") (pin "2") (pinfunction "2_2") (pintype "passive"))
      (node (ref "C32") (pin "2") (pinfunction "2_2") (pintype "passive"))
      (node (ref "C33") (pin "1") (pinfunction "1_1") (pintype "passive"))
      (node (ref "C34") (pin "-") (pinfunction "-_-") (pintype "passive"))
      (node (ref "C35") (pin "1") (pinfunction "1_1") (pintype "passive"))
      (node (ref "C36") (pin "1") (pinfunction "1_1") (pintype "passive"))
      (node (ref "C37") (pin "1") (pinfunction "1_1") (pintype "passive"))
      (node (ref "C38") (pin "1") (pinfunction "1_1") (pintype "passive"))
      (node (ref "C4") (pin "2") (pinfunction "2_2") (pintype "passive"))
      (node (ref "C41") (pin "1") (pinfunction "1_1") (pintype "passive"))
      (node (ref "C42") (pin "1") (pinfunction "1_1") (pintype "passive"))
      (node (ref "C45") (pin "2") (pinfunction "2_2") (pintype "passive"))
      (node (ref "C5") (pin "2") (pinfunction "2_2") (pintype "passive"))
      (node (ref "C6") (pin "2") (pinfunction "2_2") (pintype "passive"))
      (node (ref "C7") (pin "1") (pinfunction "1_1") (pintype "passive"))
      (node (ref "C8") (pin "1") (pinfunction "1_1") (pintype "passive"))
      (node (ref "C9") (pin "1") (pinfunction "1_1") (pintype "passive"))
      (node (ref "CP2102") (pin "3") (pinfunction "GND_3") (pintype "power_in"))
      (node (ref "CP2102") (pin "EXP") (pinfunction "GND_EXP") (pintype "power_in"))
      (node (ref "CP2102") (pin "M") (pinfunction "GND_M") (pintype "power_in"))
      (node (ref "ESC-1") (pin "1") (pinfunction "1_1") (pintype "passive"))
      (node (ref "ESC-2") (pin "1") (pinfunction "1_1") (pintype "passive"))
      (node (ref "ESC-3") (pin "1") (pinfunction "1_1") (pintype "passive"))
      (node (ref "ESC-4") (pin "1") (pinfunction "1_1") (pintype "passive"))
      (node (ref "ESP8266") (pin "GND") (pinfunction "GND_GND") (pintype "bidirectional"))
      (node (ref "MPU6050") (pin "1") (pinfunction "CLKIN_1") (pintype "input"))
      (node (ref "MPU6050") (pin "11") (pinfunction "FSYNC_11") (pintype "input"))
      (node (ref "MPU6050") (pin "18") (pinfunction "GND_18") (pintype "power_in"))
      (node (ref "MPU6050") (pin "9") (pinfunction "AD0_9") (pintype "input"))
      (node (ref "NRF24L01") (pin "14") (pinfunction "VSS_14") (pintype "power_in"))
      (node (ref "NRF24L01") (pin "17") (pinfunction "VSS_17") (pintype "power_in"))
      (node (ref "NRF24L01") (pin "20") (pinfunction "VSS_20") (pintype "power_in"))
      (node (ref "NRF24L01") (pin "21") (pinfunction "EP_21") (pintype "power_in"))
      (node (ref "NRF24L01") (pin "8") (pinfunction "VSS_8") (pintype "power_in"))
      (node (ref "R14") (pin "1") (pinfunction "1_1") (pintype "passive"))
      (node (ref "R2") (pin "2") (pinfunction "2_2") (pintype "passive"))
      (node (ref "R22") (pin "1") (pinfunction "1_1") (pintype "passive"))
      (node (ref "R23") (pin "2") (pinfunction "2_2") (pintype "passive"))
      (node (ref "R24") (pin "2") (pinfunction "2_2") (pintype "passive"))
      (node (ref "R25") (pin "2") (pinfunction "2_2") (pintype "passive"))
      (node (ref "R26") (pin "2") (pinfunction "2_2") (pintype "passive"))
      (node (ref "R27") (pin "2") (pinfunction "2_2") (pintype "passive"))
      (node (ref "RFX2401C") (pin "11") (pinfunction "GND_11") (pintype "power_in"))
      (node (ref "RFX2401C") (pin "17") (pinfunction "GND_17") (pintype "power_in"))
      (node (ref "RFX2401C") (pin "2") (pinfunction "GND_2") (pintype "power_in"))
      (node (ref "RFX2401C") (pin "3") (pinfunction "GND_3") (pintype "power_in"))
      (node (ref "RFX2401C") (pin "8") (pinfunction "GND_8") (pintype "power_in"))
      (node (ref "RFX2401C") (pin "9") (pinfunction "GND_9") (pintype "power_in"))
      (node (ref "U1") (pin "23") (pinfunction "VSS_1_23") (pintype "power_in"))
      (node (ref "U1") (pin "35") (pinfunction "VSS_2_35") (pintype "power_in"))
      (node (ref "U1") (pin "47") (pinfunction "VSS_3_47") (pintype "power_in"))
      (node (ref "U1") (pin "8") (pinfunction "VSSA_8") (pintype "power_in"))
      (node (ref "U4") (pin "1") (pinfunction "ADJ_1") (pintype "input"))
      (node (ref "USB-PWR") (pin "C") (pinfunction "C_C") (pintype "passive"))
      (node (ref "X1") (pin "11") (pinfunction "11_11") (pintype "passive"))
      (node (ref "X1") (pin "5") (pinfunction "5_5") (pintype "passive"))
      (node (ref "X1") (pin "7") (pinfunction "7_7") (pintype "passive"))
      (node (ref "X2") (pin "2") (pinfunction "2_2") (pintype "passive"))
      (node (ref "X2") (pin "3") (pinfunction "2_3") (pintype "passive"))
      (node (ref "X2") (pin "4") (pinfunction "2_4") (pintype "passive"))
      (node (ref "X2") (pin "5") (pinfunction "2_5") (pintype "passive"))
      (node (ref "X3") (pin "5") (pinfunction "5_5") (pintype "passive"))
      (node (ref "X3") (pin "M1") (pinfunction "S1_M1") (pintype "passive"))
      (node (ref "X3") (pin "M2") (pinfunction "S2_M2") (pintype "passive"))
      (node (ref "X3") (pin "M3") (pinfunction "S3_M3") (pintype "passive"))
      (node (ref "X3") (pin "M4") (pinfunction "S4_M4") (pintype "passive"))
    )
    (net (code "11") (name "GPIO0") (class "Default")
      (node (ref "ESP8266") (pin "GPIO0") (pinfunction "GPIO0_GPIO0") (pintype "bidirectional"))
      (node (ref "R6") (pin "1") (pinfunction "1_1") (pintype "passive"))
      (node (ref "T4") (pin "C") (pinfunction "C_C") (pintype "passive"))
    )
    (net (code "12") (name "GPIO2") (class "Default")
      (node (ref "ESP8266") (pin "GPIO2") (pinfunction "GPIO2_GPIO2") (pintype "bidirectional"))
      (node (ref "R7") (pin "1") (pinfunction "1_1") (pintype "passive"))
    )
    (net (code "13") (name "GPIO14") (class "Default")
      (node (ref "ESP8266") (pin "GPIO14") (pinfunction "GPIO14_GPIO14") (pintype "bidirectional"))
    )
    (net (code "14") (name "GPIO15") (class "Default")
      (node (ref "ESP8266") (pin "GPIO15") (pinfunction "GPIO15_GPIO15") (pintype "bidirectional"))
      (node (ref "R2") (pin "1") (pinfunction "1_1") (pintype "passive"))
    )
    (net (code "15") (name "GPIO16") (class "Default")
      (node (ref "ESP8266") (pin "GPIO16") (pinfunction "GPIO16_GPIO16") (pintype "bidirectional"))
    )
    (net (code "16") (name "NRF-ANT") (class "Default")
      (node (ref "C27") (pin "2") (pinfunction "2_2") (pintype "passive"))
      (node (ref "C28") (pin "2") (pinfunction "2_2") (pintype "passive"))
      (node (ref "RFX2401C") (pin "4") (pinfunction "TXRX_4") (pintype "bidirectional"))
    )
    (net (code "17") (name "NRST") (class "Default")
      (node (ref "C10") (pin "2") (pinfunction "2_2") (pintype "passive"))
      (node (ref "ESP8266") (pin "GPIO13") (pinfunction "GPIO13_GPIO13") (pintype "bidirectional"))
      (node (ref "R3") (pin "2") (pinfunction "2_2") (pintype "passive"))
      (node (ref "U1") (pin "7") (pinfunction "NRST_7") (pintype "bidirectional"))
      (node (ref "X1") (pin "12") (pinfunction "12_12") (pintype "passive"))
    )
    (net (code "18") (name "Net-(BME280-CSB)") (class "Default")
      (node (ref "BME280") (pin "2") (pinfunction "CSB_2") (pintype "input"))
      (node (ref "R21") (pin "1") (pinfunction "1_1") (pintype "passive"))
    )
    (net (code "19") (name "Net-(BME280-SDO)") (class "Default")
      (node (ref "BME280") (pin "5") (pinfunction "SDO_5") (pintype "bidirectional"))
      (node (ref "R22") (pin "2") (pinfunction "2_2") (pintype "passive"))
    )
    (net (code "20") (name "Net-(C9-Pad2)") (class "Default")
      (node (ref "C9") (pin "2") (pinfunction "2_2") (pintype "passive"))
      (node (ref "Q2") (pin "1") (pinfunction "1_1") (pintype "passive"))
      (node (ref "R4") (pin "1") (pinfunction "1_1") (pintype "passive"))
    )
    (net (code "21") (name "Net-(C18-Pad2)") (class "Default")
      (node (ref "C18") (pin "2") (pinfunction "2_2") (pintype "passive"))
      (node (ref "C20") (pin "2") (pinfunction "2_2") (pintype "passive"))
      (node (ref "L1") (pin "2") (pinfunction "2_2") (pintype "passive"))
      (node (ref "L2") (pin "1") (pinfunction "1_1") (pintype "passive"))
    )
    (net (code "22") (name "Net-(C21-Pad2)") (class "Default")
      (node (ref "C21") (pin "2") (pinfunction "2_2") (pintype "passive"))
      (node (ref "L2") (pin "2") (pinfunction "2_2") (pintype "passive"))
      (node (ref "X2") (pin "1") (pinfunction "1_1") (pintype "passive"))
    )
    (net (code "23") (name "Net-(C27-Pad1)") (class "Default")
      (node (ref "C27") (pin "1") (pinfunction "1_1") (pintype "passive"))
      (node (ref "L6") (pin "2") (pinfunction "2_2") (pintype "passive"))
    )
    (net (code "24") (name "Net-(CP2102-D+)") (class "Default")
      (node (ref "CP2102") (pin "4") (pinfunction "D+_4") (pintype "bidirectional"))
      (node (ref "X3") (pin "3") (pinfunction "3_3") (pintype "passive"))
    )
    (net (code "25") (name "Net-(CP2102-D-)") (class "Default")
      (node (ref "CP2102") (pin "5") (pinfunction "D-_5") (pintype "bidirectional"))
      (node (ref "X3") (pin "2") (pinfunction "2_2") (pintype "passive"))
    )
    (net (code "26") (name "Net-(CP2102-~{RST})") (class "Default")
      (node (ref "CP2102") (pin "9") (pinfunction "~{RST}_9") (pintype "bidirectional"))
      (node (ref "R12") (pin "1") (pinfunction "1_1") (pintype "passive"))
    )
    (net (code "27") (name "Net-(FERRIT-Pad1)") (class "Default")
      (node (ref "FERRIT") (pin "1") (pinfunction "1_1") (pintype "passive"))
      (node (ref "X3") (pin "1") (pinfunction "1_1") (pintype "passive"))
    )
    (net (code "28") (name "Net-(LED1-PadC)") (class "Default")
      (node (ref "LED1") (pin "C") (pinfunction "C_C") (pintype "passive"))
      (node (ref "R24") (pin "1") (pinfunction "1_1") (pintype "passive"))
    )
    (net (code "29") (name "Net-(LED2-PadC)") (class "Default")
      (node (ref "LED2") (pin "C") (pinfunction "C_C") (pintype "passive"))
      (node (ref "R25") (pin "1") (pinfunction "1_1") (pintype "passive"))
    )
    (net (code "30") (name "Net-(LED3-PadC)") (class "Default")
      (node (ref "LED3") (pin "C") (pinfunction "C_C") (pintype "passive"))
      (node (ref "R26") (pin "1") (pinfunction "1_1") (pintype "passive"))
    )
    (net (code "31") (name "Net-(LED4-PadC)") (class "Default")
      (node (ref "LED4") (pin "C") (pinfunction "C_C") (pintype "passive"))
      (node (ref "R27") (pin "1") (pinfunction "1_1") (pintype "passive"))
    )
    (net (code "32") (name "Net-(LIPO+-P)") (class "Default")
      (node (ref "LIPO+") (pin "1") (pinfunction "P_1") (pintype "passive"))
      (node (ref "R17") (pin "1") (pinfunction "1_1") (pintype "passive"))
    )
    (net (code "33") (name "Net-(LIPO--P)") (class "Default")
      (node (ref "LIPO-") (pin "1") (pinfunction "P_1") (pintype "passive"))
      (node (ref "R18") (pin "2") (pinfunction "2_2") (pintype "passive"))
    )
    (net (code "34") (name "Net-(MPU6050-CPOUT)") (class "Default")
      (node (ref "C35") (pin "2") (pinfunction "2_2") (pintype "passive"))
      (node (ref "MPU6050") (pin "20") (pinfunction "CPOUT_20") (pintype "passive"))
    )
    (net (code "35") (name "Net-(MPU6050-REGOUT)") (class "Default")
      (node (ref "C36") (pin "2") (pinfunction "2_2") (pintype "passive"))
      (node (ref "MPU6050") (pin "10") (pinfunction "REGOUT_10") (pintype "passive"))
    )
    (net (code "36") (name "Net-(NRF24L01-ANT1)") (class "Default")
      (node (ref "L4") (pin "2") (pinfunction "2_2") (pintype "passive"))
      (node (ref "L5") (pin "1") (pinfunction "1_1") (pintype "passive"))
      (node (ref "NRF24L01") (pin "12") (pinfunction "ANT1_12") (pintype "bidirectional"))
    )
    (net (code "37") (name "Net-(NRF24L01-ANT2)") (class "Default")
      (node (ref "L4") (pin "1") (pinfunction "1_1") (pintype "passive"))
      (node (ref "L6") (pin "1") (pinfunction "1_1") (pintype "passive"))
      (node (ref "NRF24L01") (pin "13") (pinfunction "ANT2_13") (pintype "bidirectional"))
    )
    (net (code "38") (name "Net-(NRF24L01-DVDD)") (class "Default")
      (node (ref "C24") (pin "2") (pinfunction "2_2") (pintype "passive"))
      (node (ref "NRF24L01") (pin "19") (pinfunction "DVDD_19") (pintype "power_in"))
    )
    (net (code "39") (name "Net-(NRF24L01-IREF)") (class "Default")
      (node (ref "NRF24L01") (pin "16") (pinfunction "IREF_16") (pintype "input"))
      (node (ref "R14") (pin "2") (pinfunction "2_2") (pintype "passive"))
    )
    (net (code "40") (name "Net-(NRF24L01-XC1)") (class "Default")
      (node (ref "C25") (pin "2") (pinfunction "2_2") (pintype "passive"))
      (node (ref "NRF24L01") (pin "10") (pinfunction "XC1_10") (pintype "input"))
      (node (ref "Q3") (pin "1") (pinfunction "1_1") (pintype "passive"))
    )
    (net (code "41") (name "Net-(NRF24L01-XC2)") (class "Default")
      (node (ref "C26") (pin "2") (pinfunction "2_2") (pintype "passive"))
      (node (ref "NRF24L01") (pin "9") (pinfunction "XC2_9") (pintype "output"))
      (node (ref "Q3") (pin "2") (pinfunction "2_2") (pintype "passive"))
    )
    (net (code "42") (name "Net-(R1-Pad1)") (class "Default")
      (node (ref "R1") (pin "1") (pinfunction "1_1") (pintype "passive"))
      (node (ref "T3") (pin "B") (pinfunction "B_B") (pintype "passive"))
    )
    (net (code "43") (name "Net-(R9-Pad1)") (class "Default")
      (node (ref "R9") (pin "1") (pinfunction "1_1") (pintype "passive"))
      (node (ref "T4") (pin "B") (pinfunction "B_B") (pintype "passive"))
    )
    (net (code "44") (name "Net-(R50-Pad2)") (class "Default")
      (node (ref "R50") (pin "2") (pinfunction "2_2") (pintype "passive"))
      (node (ref "USB-PWR") (pin "A") (pinfunction "A_A") (pintype "passive"))
    )
    (net (code "45") (name "Net-(RFX2401C-ANT)") (class "Default")
      (node (ref "C17") (pin "2") (pinfunction "2_2") (pintype "passive"))
      (node (ref "C19") (pin "2") (pinfunction "2_2") (pintype "passive"))
      (node (ref "L1") (pin "1") (pinfunction "1_1") (pintype "passive"))
      (node (ref "RFX2401C") (pin "10") (pinfunction "ANT_10") (pintype "passive"))
    )
    (net (code "46") (name "Net-(RFX2401C-RXEN)") (class "Default")
      (node (ref "R13") (pin "2") (pinfunction "2_2") (pintype "passive"))
      (node (ref "RFX2401C") (pin "6") (pinfunction "RXEN_6") (pintype "input"))
    )
    (net (code "47") (name "Net-(RFX2401C-TXEN)") (class "Default")
      (node (ref "R15") (pin "2") (pinfunction "2_2") (pintype "passive"))
      (node (ref "RFX2401C") (pin "5") (pinfunction "TXEN_5") (pintype "input"))
    )
    (net (code "48") (name "OSC_IN") (class "Default")
      (node (ref "C8") (pin "2") (pinfunction "2_2") (pintype "passive"))
      (node (ref "Q2") (pin "2") (pinfunction "2_2") (pintype "passive"))
      (node (ref "U1") (pin "5") (pinfunction "OSC_IN_5") (pintype "input"))
    )
    (net (code "49") (name "OSC_OUT") (class "Default")
      (node (ref "R4") (pin "2") (pinfunction "2_2") (pintype "passive"))
      (node (ref "U1") (pin "6") (pinfunction "OSC_OUT_6") (pintype "output"))
    )
    (net (code "50") (name "PA0-WKUP") (class "Default")
      (node (ref "U1") (pin "10") (pinfunction "PA0-WKUP_10") (pintype "bidirectional"))
    )
    (net (code "51") (name "PA1-LIPO-IN") (class "Default")
      (node (ref "R17") (pin "2") (pinfunction "2_2") (pintype "passive"))
      (node (ref "R18") (pin "1") (pinfunction "1_1") (pintype "passive"))
      (node (ref "U1") (pin "11") (pinfunction "PA1_11") (pintype "bidirectional"))
    )
    (net (code "52") (name "PA2") (class "Default")
      (node (ref "U1") (pin "12") (pinfunction "PA2_12") (pintype "bidirectional"))
    )
    (net (code "53") (name "PA3") (class "Default")
      (node (ref "U1") (pin "13") (pinfunction "PA3_13") (pintype "bidirectional"))
    )
    (net (code "54") (name "PA4") (class "Default")
      (node (ref "U1") (pin "14") (pinfunction "PA4_14") (pintype "bidirectional"))
    )
    (net (code "55") (name "PA5") (class "Default")
      (node (ref "U1") (pin "15") (pinfunction "PA5_15") (pintype "bidirectional"))
    )
    (net (code "56") (name "PA6-LED-1") (class "Default")
      (node (ref "LED3") (pin "A") (pinfunction "A_A") (pintype "passive"))
      (node (ref "U1") (pin "16") (pinfunction "PA6_16") (pintype "bidirectional"))
    )
    (net (code "57") (name "PA7-LED-2") (class "Default")
      (node (ref "LED4") (pin "A") (pinfunction "A_A") (pintype "passive"))
      (node (ref "U1") (pin "17") (pinfunction "PA7_17") (pintype "bidirectional"))
    )
    (net (code "58") (name "PA8-RF-TXEN") (class "Default")
      (node (ref "R15") (pin "1") (pinfunction "1_1") (pintype "passive"))
      (node (ref "U1") (pin "29") (pinfunction "PA8_29") (pintype "bidirectional"))
    )
    (net (code "59") (name "PA9-TX") (class "Default")
      (node (ref "ESP-MCU-RX") (pin "1") (pinfunction "1_1") (pintype "passive"))
      (node (ref "U1") (pin "30") (pinfunction "PA9_30") (pintype "bidirectional"))
    )
    (net (code "60") (name "PA10-RX") (class "Default")
      (node (ref "ESP-MCU-TX") (pin "1") (pinfunction "1_1") (pintype "passive"))
      (node (ref "U1") (pin "31") (pinfunction "PA10_31") (pintype "bidirectional"))
    )
    (net (code "61") (name "PA11") (class "Default")
      (node (ref "U1") (pin "32") (pinfunction "PA11_32") (pintype "bidirectional"))
    )
    (net (code "62") (name "PA12") (class "Default")
      (node (ref "U1") (pin "33") (pinfunction "PA12_33") (pintype "bidirectional"))
    )
    (net (code "63") (name "PA15") (class "Default")
      (node (ref "U1") (pin "38") (pinfunction "PA15_38") (pintype "bidirectional"))
    )
    (net (code "64") (name "PB0-PWM-3") (class "Default")
      (node (ref "ESC-1") (pin "2") (pinfunction "2_2") (pintype "passive"))
      (node (ref "U1") (pin "18") (pinfunction "PB0_18") (pintype "bidirectional"))
    )
    (net (code "65") (name "PB1-PWM-4") (class "Default")
      (node (ref "ESC-2") (pin "2") (pinfunction "2_2") (pintype "passive"))
      (node (ref "U1") (pin "19") (pinfunction "PB1_19") (pintype "bidirectional"))
    )
    (net (code "66") (name "PB2-BOOT1") (class "Default")
      (node (ref "R23") (pin "1") (pinfunction "1_1") (pintype "passive"))
      (node (ref "U1") (pin "20") (pinfunction "PB2_20") (pintype "bidirectional"))
    )
    (net (code "67") (name "PB4-PWM-1") (class "Default")
      (node (ref "ESC-3") (pin "2") (pinfunction "2_2") (pintype "passive"))
      (node (ref "U1") (pin "40") (pinfunction "PB4_40") (pintype "bidirectional"))
    )
    (net (code "68") (name "PB5-PWM-2") (class "Default")
      (node (ref "ESC-4") (pin "2") (pinfunction "2_2") (pintype "passive"))
      (node (ref "U1") (pin "41") (pinfunction "PB5_41") (pintype "bidirectional"))
    )
    (net (code "69") (name "PB6-I2C-SCL") (class "Default")
      (node (ref "BME280") (pin "4") (pinfunction "SCK_4") (pintype "input"))
      (node (ref "MPU6050") (pin "23") (pinfunction "SCL_23") (pintype "input"))
      (node (ref "R19") (pin "1") (pinfunction "1_1") (pintype "passive"))
      (node (ref "U1") (pin "42") (pinfunction "PB6_42") (pintype "bidirectional"))
    )
    (net (code "70") (name "PB7-I2C-SDA") (class "Default")
      (node (ref "BME280") (pin "3") (pinfunction "SDI_3") (pintype "bidirectional"))
      (node (ref "MPU6050") (pin "24") (pinfunction "SDA_24") (pintype "bidirectional"))
      (node (ref "R20") (pin "1") (pinfunction "1_1") (pintype "passive"))
      (node (ref "U1") (pin "43") (pinfunction "PB7_43") (pintype "bidirectional"))
    )
    (net (code "71") (name "PB8-MEMS-INT") (class "Default")
      (node (ref "MPU6050") (pin "12") (pinfunction "INT_12") (pintype "output"))
      (node (ref "U1") (pin "45") (pinfunction "PB8_45") (pintype "bidirectional"))
    )
    (net (code "72") (name "PB9") (class "Default")
      (node (ref "U1") (pin "46") (pinfunction "PB9_46") (pintype "bidirectional"))
    )
    (net (code "73") (name "PB10-NRF-IRQ") (class "Default")
      (node (ref "NRF24L01") (pin "6") (pinfunction "~{IRQ}_6") (pintype "output"))
      (node (ref "U1") (pin "21") (pinfunction "PB10_21") (pintype "bidirectional"))
    )
    (net (code "74") (name "PB11-NRF-CE") (class "Default")
      (node (ref "NRF24L01") (pin "1") (pinfunction "CE_1") (pintype "input"))
      (node (ref "U1") (pin "22") (pinfunction "PB11_22") (pintype "bidirectional"))
    )
    (net (code "75") (name "PB12-NRF-CS") (class "Default")
      (node (ref "NRF24L01") (pin "2") (pinfunction "CSN_2") (pintype "input"))
      (node (ref "U1") (pin "25") (pinfunction "PB12_25") (pintype "bidirectional"))
    )
    (net (code "76") (name "PB13-SPI-SCK") (class "Default")
      (node (ref "NRF24L01") (pin "3") (pinfunction "SCK_3") (pintype "input"))
      (node (ref "U1") (pin "26") (pinfunction "PB13_26") (pintype "bidirectional"))
    )
    (net (code "77") (name "PB14-SPI-MISO") (class "Default")
      (node (ref "NRF24L01") (pin "5") (pinfunction "MISO_5") (pintype "output"))
      (node (ref "U1") (pin "27") (pinfunction "PB14_27") (pintype "bidirectional"))
    )
    (net (code "78") (name "PB15-SPI-MOSI") (class "Default")
      (node (ref "NRF24L01") (pin "4") (pinfunction "MOSI_4") (pintype "input"))
      (node (ref "U1") (pin "28") (pinfunction "PB15_28") (pintype "bidirectional"))
    )
    (net (code "79") (name "PC13") (class "Default")
      (node (ref "U1") (pin "2") (pinfunction "PC13_2") (pintype "bidirectional"))
    )
    (net (code "80") (name "PC14-OSC32_IN") (class "Default")
      (node (ref "U1") (pin "3") (pinfunction "PC14-OSC32_IN_3") (pintype "bidirectional"))
    )
    (net (code "81") (name "PC15-OSC32_OUT") (class "Default")
      (node (ref "U1") (pin "4") (pinfunction "PC15-OSC32_OUT_4") (pintype "bidirectional"))
    )
    (net (code "82") (name "RESET") (class "Default")
      (node (ref "C11") (pin "1") (pinfunction "1_1") (pintype "passive"))
      (node (ref "ESP8266") (pin "REST") (pinfunction "RESET_REST") (pintype "bidirectional"))
      (node (ref "R5") (pin "1") (pinfunction "1_1") (pintype "passive"))
      (node (ref "T3") (pin "C") (pinfunction "C_C") (pintype "passive"))
    )
    (net (code "83") (name "RTS") (class "Default")
      (node (ref "CP2102") (pin "24") (pinfunction "RTS_24") (pintype "output"))
      (node (ref "R9") (pin "2") (pinfunction "2_2") (pintype "passive"))
      (node (ref "T3") (pin "E") (pinfunction "E_E") (pintype "passive"))
    )
    (net (code "84") (name "RX") (class "Default")
      (node (ref "ESP-MCU-RX") (pin "2") (pinfunction "2_2") (pintype "passive"))
      (node (ref "ESP8266") (pin "RX") (pinfunction "RX_RX") (pintype "bidirectional"))
      (node (ref "R11") (pin "1") (pinfunction "1_1") (pintype "passive"))
    )
    (net (code "85") (name "RXD") (class "Default")
      (node (ref "CP2102") (pin "25") (pinfunction "RXD_25") (pintype "input"))
      (node (ref "R10") (pin "2") (pinfunction "2_2") (pintype "passive"))
    )
    (net (code "86") (name "SWCLK") (class "Default")
      (node (ref "U1") (pin "37") (pinfunction "PA14_37") (pintype "bidirectional"))
      (node (ref "X1") (pin "6") (pinfunction "6_6") (pintype "passive"))
    )
    (net (code "87") (name "SWDIO") (class "Default")
      (node (ref "U1") (pin "34") (pinfunction "PA13_34") (pintype "bidirectional"))
      (node (ref "X1") (pin "4") (pinfunction "4_4") (pintype "passive"))
    )
    (net (code "88") (name "SWO") (class "Default")
      (node (ref "U1") (pin "39") (pinfunction "PB3_39") (pintype "bidirectional"))
      (node (ref "X1") (pin "8") (pinfunction "8_8") (pintype "passive"))
    )
    (net (code "89") (name "TX") (class "Default")
      (node (ref "ESP-MCU-TX") (pin "2") (pinfunction "2_2") (pintype "passive"))
      (node (ref "ESP8266") (pin "TX") (pinfunction "TX_TX") (pintype "bidirectional"))
      (node (ref "R10") (pin "1") (pinfunction "1_1") (pintype "passive"))
    )
    (net (code "90") (name "TXD") (class "Default")
      (node (ref "CP2102") (pin "26") (pinfunction "TXD_26") (pintype "output"))
      (node (ref "R11") (pin "2") (pinfunction "2_2") (pintype "passive"))
    )
    (net (code "91") (name "VBUS") (class "Default")
      (node (ref "C31") (pin "1") (pinfunction "1_1") (pintype "passive"))
      (node (ref "C32") (pin "1") (pinfunction "1_1") (pintype "passive"))
      (node (ref "CP2102") (pin "7") (pinfunction "REGIN_7") (pintype "passive"))
      (node (ref "CP2102") (pin "8") (pinfunction "VBUS_8") (pintype "input"))
      (node (ref "D1") (pin "A") (pinfunction "A_A") (pintype "passive"))
      (node (ref "FERRIT") (pin "2") (pinfunction "2_2") (pintype "passive"))
      (node (ref "R12") (pin "2") (pinfunction "2_2") (pintype "passive"))
      (node (ref "R50") (pin "1") (pinfunction "1_1") (pintype "passive"))
    )
    (net (code "92") (name "VDD_PA") (class "Default")
      (node (ref "C29") (pin "2") (pinfunction "2_2") (pintype "passive"))
      (node (ref "C30") (pin "2") (pinfunction "2_2") (pintype "passive"))
      (node (ref "L5") (pin "2") (pinfunction "2_2") (pintype "passive"))
      (node (ref "NRF24L01") (pin "11") (pinfunction "VDD_PA_11") (pintype "power_in"))
      (node (ref "R13") (pin "1") (pinfunction "1_1") (pintype "passive"))
    )
    (net (code "93") (name "unconnected-(CP2102-CTS-Pad23)") (class "Default")
      (node (ref "CP2102") (pin "23") (pinfunction "CTS_23") (pintype "input"))
    )
    (net (code "94") (name "unconnected-(CP2102-DCD-Pad1)") (class "Default")
      (node (ref "CP2102") (pin "1") (pinfunction "DCD_1") (pintype "input"))
    )
    (net (code "95") (name "unconnected-(CP2102-DSR-Pad27)") (class "Default")
      (node (ref "CP2102") (pin "27") (pinfunction "DSR_27") (pintype "input"))
    )
    (net (code "96") (name "unconnected-(CP2102-RI-Pad2)") (class "Default")
      (node (ref "CP2102") (pin "2") (pinfunction "RI_2") (pintype "input"))
    )
    (net (code "97") (name "unconnected-(CP2102-SUSPEND-Pad12)") (class "Default")
      (node (ref "CP2102") (pin "12") (pinfunction "SUSPEND_12") (pintype "output"))
    )
    (net (code "98") (name "unconnected-(CP2102-~{SUSPEND}-Pad11)") (class "Default")
      (node (ref "CP2102") (pin "11") (pinfunction "~{SUSPEND}_11") (pintype "output"))
    )
    (net (code "99") (name "unconnected-(MPU6050-AUX_CL-Pad7)") (class "Default")
      (node (ref "MPU6050") (pin "7") (pinfunction "AUX_CL_7") (pintype "input"))
    )
    (net (code "100") (name "unconnected-(MPU6050-AUX_DA-Pad6)") (class "Default")
      (node (ref "MPU6050") (pin "6") (pinfunction "AUX_DA_6") (pintype "bidirectional"))
    )
    (net (code "101") (name "unconnected-(MPU6050-RESV-Pad19)") (class "Default")
      (node (ref "MPU6050") (pin "19") (pinfunction "RESV_19") (pintype "passive"))
    )
    (net (code "102") (name "unconnected-(MPU6050-RESV-Pad21)") (class "Default")
      (node (ref "MPU6050") (pin "21") (pinfunction "RESV_21") (pintype "passive"))
    )
    (net (code "103") (name "unconnected-(MPU6050-RESV-Pad22)") (class "Default")
      (node (ref "MPU6050") (pin "22") (pinfunction "RESV_22") (pintype "passive"))
    )
    (net (code "104") (name "unconnected-(X1-Pad1)") (class "Default")
      (node (ref "X1") (pin "1") (pinfunction "1_1") (pintype "passive"))
    )
    (net (code "105") (name "unconnected-(X1-Pad2)") (class "Default")
      (node (ref "X1") (pin "2") (pinfunction "2_2") (pintype "passive"))
    )
    (net (code "106") (name "unconnected-(X1-Pad9)") (class "Default")
      (node (ref "X1") (pin "9") (pinfunction "9_9") (pintype "passive"))
    )
    (net (code "107") (name "unconnected-(X1-Pad10)") (class "Default")
      (node (ref "X1") (pin "10") (pinfunction "10_10") (pintype "passive"))
    )
    (net (code "108") (name "unconnected-(X1-Pad13)") (class "Default")
      (node (ref "X1") (pin "13") (pinfunction "13_13") (pintype "passive"))
    )
    (net (code "109") (name "unconnected-(X1-Pad14)") (class "Default")
      (node (ref "X1") (pin "14") (pinfunction "14_14") (pintype "passive"))
    )
    (net (code "110") (name "unconnected-(X3-Pad4)") (class "Default")
      (node (ref "X3") (pin "4") (pinfunction "4_4") (pintype "passive"))
    )
  )
)
